# ReuseBlock___2025-12-05.net
KiCad netlist of a schematic drawn in EasyEDA Pro
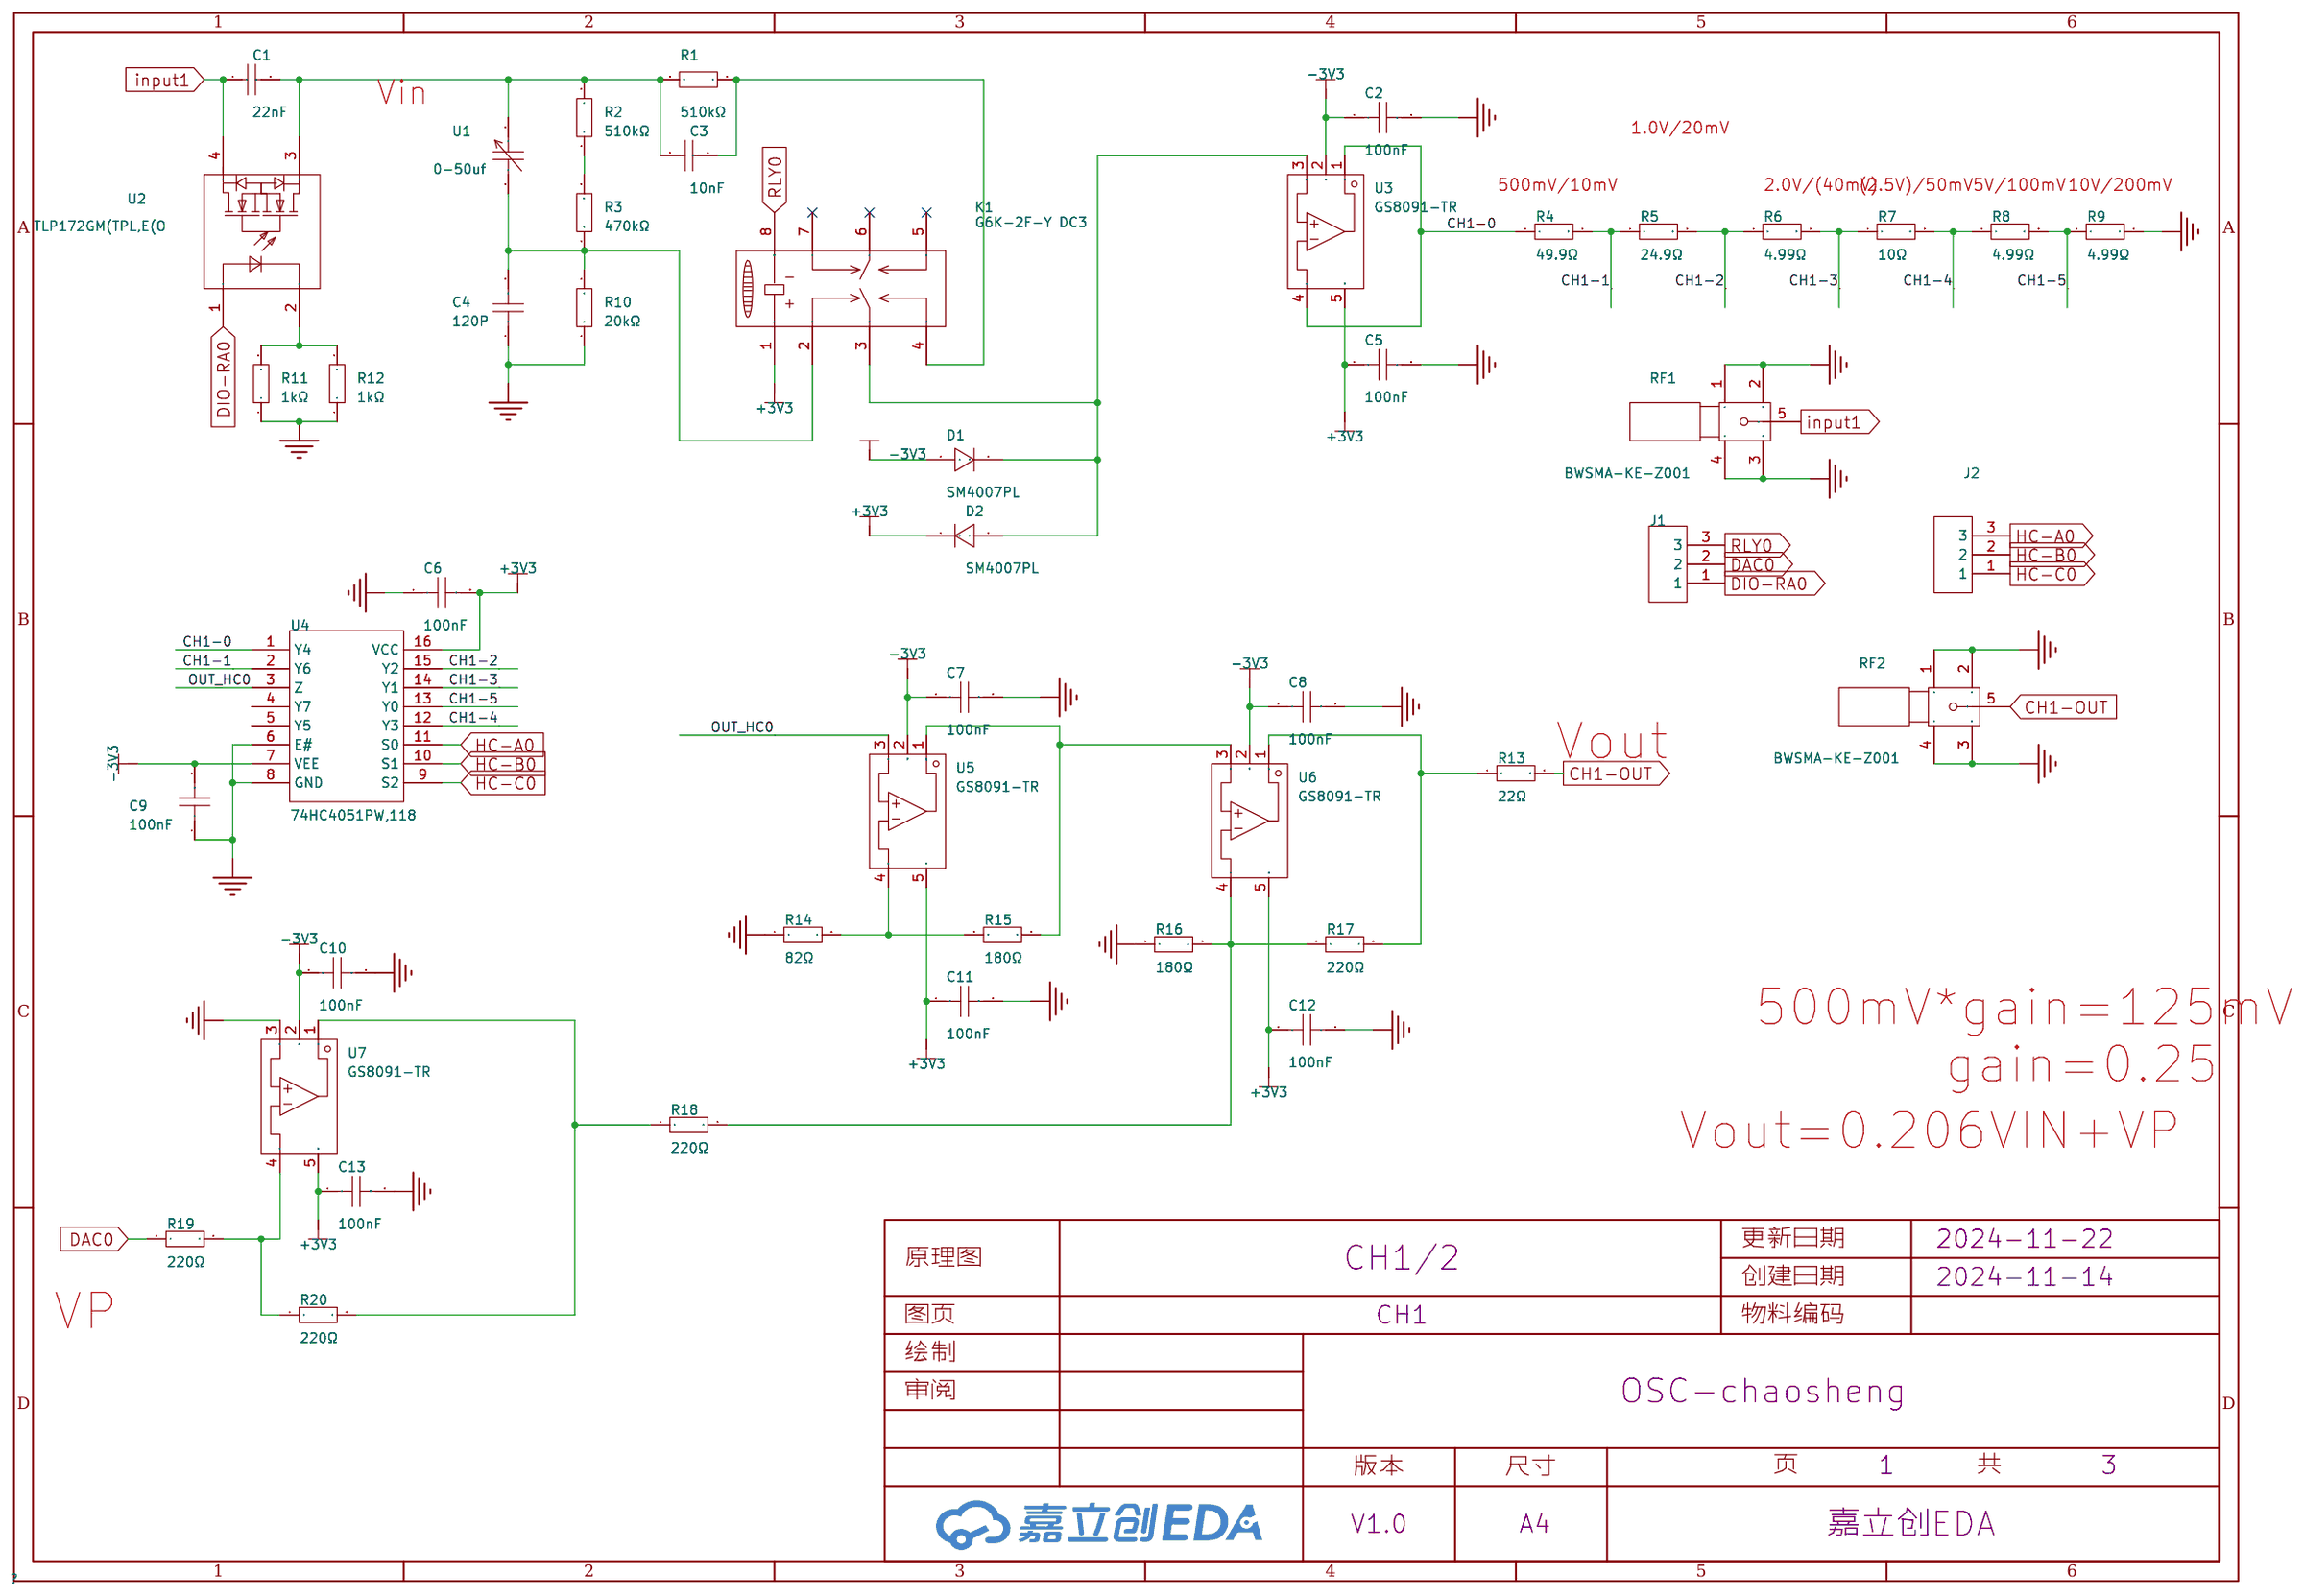
[diagram p0: CH1]
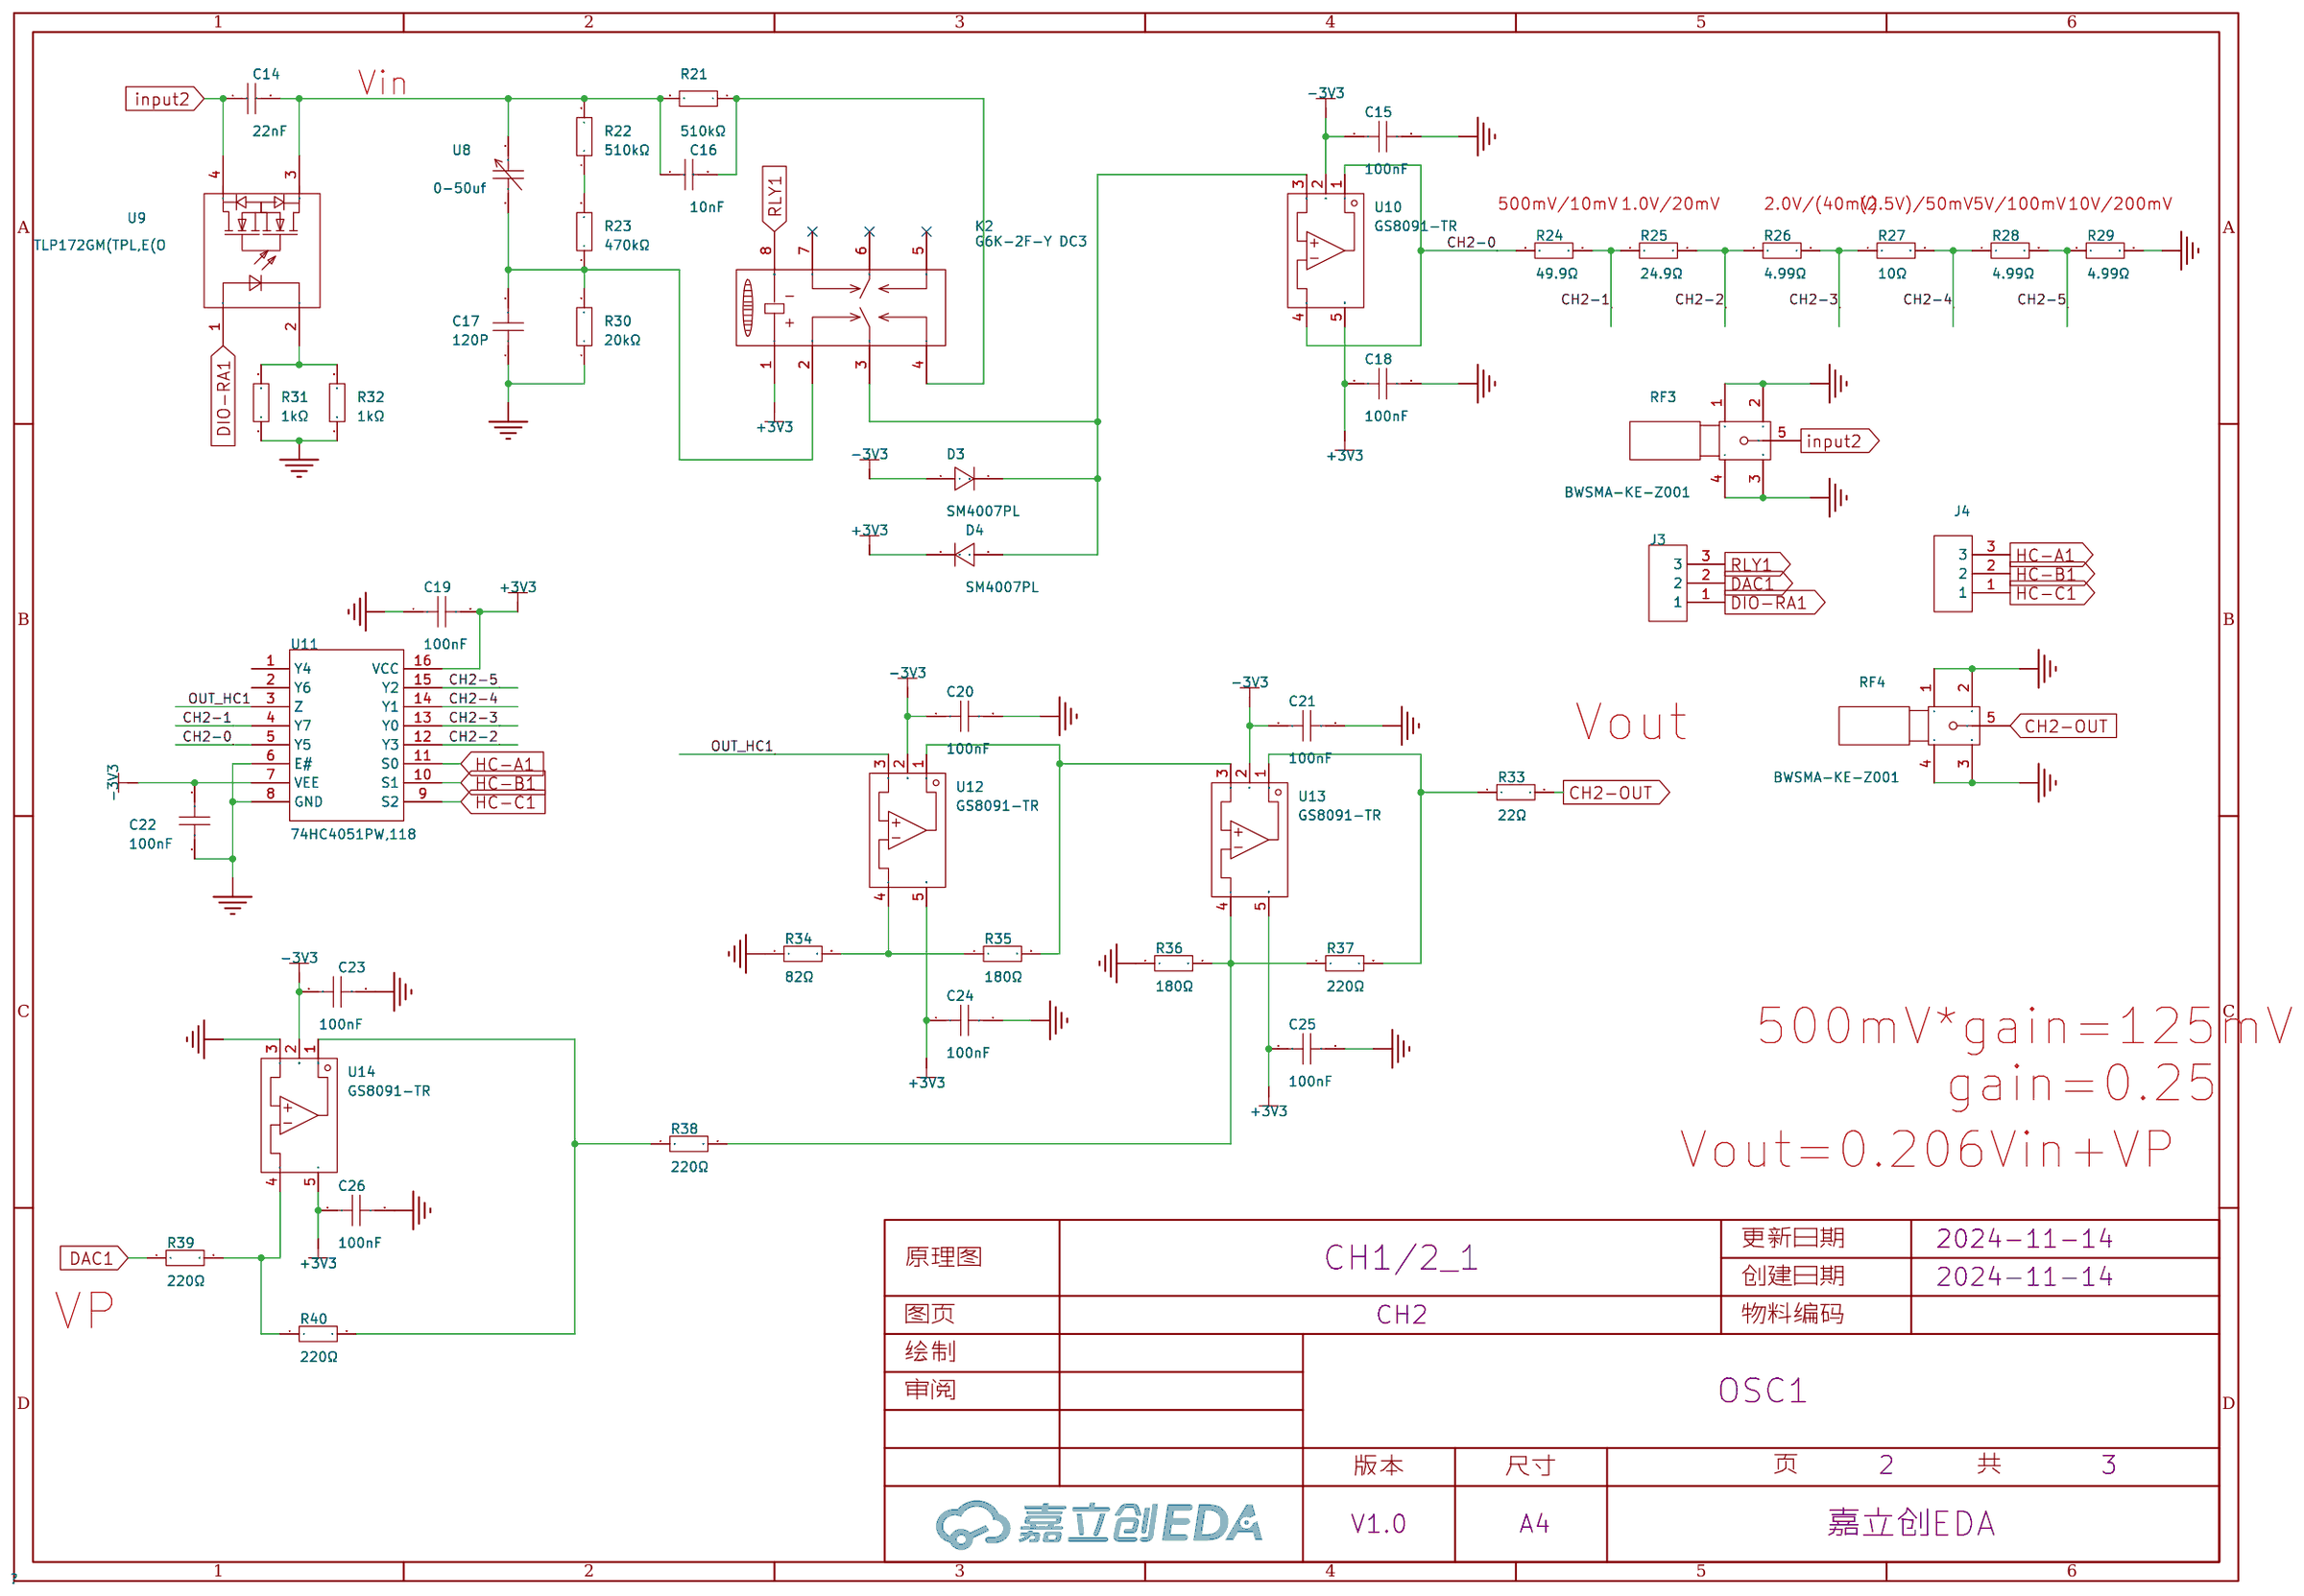
[diagram p1: CH2]
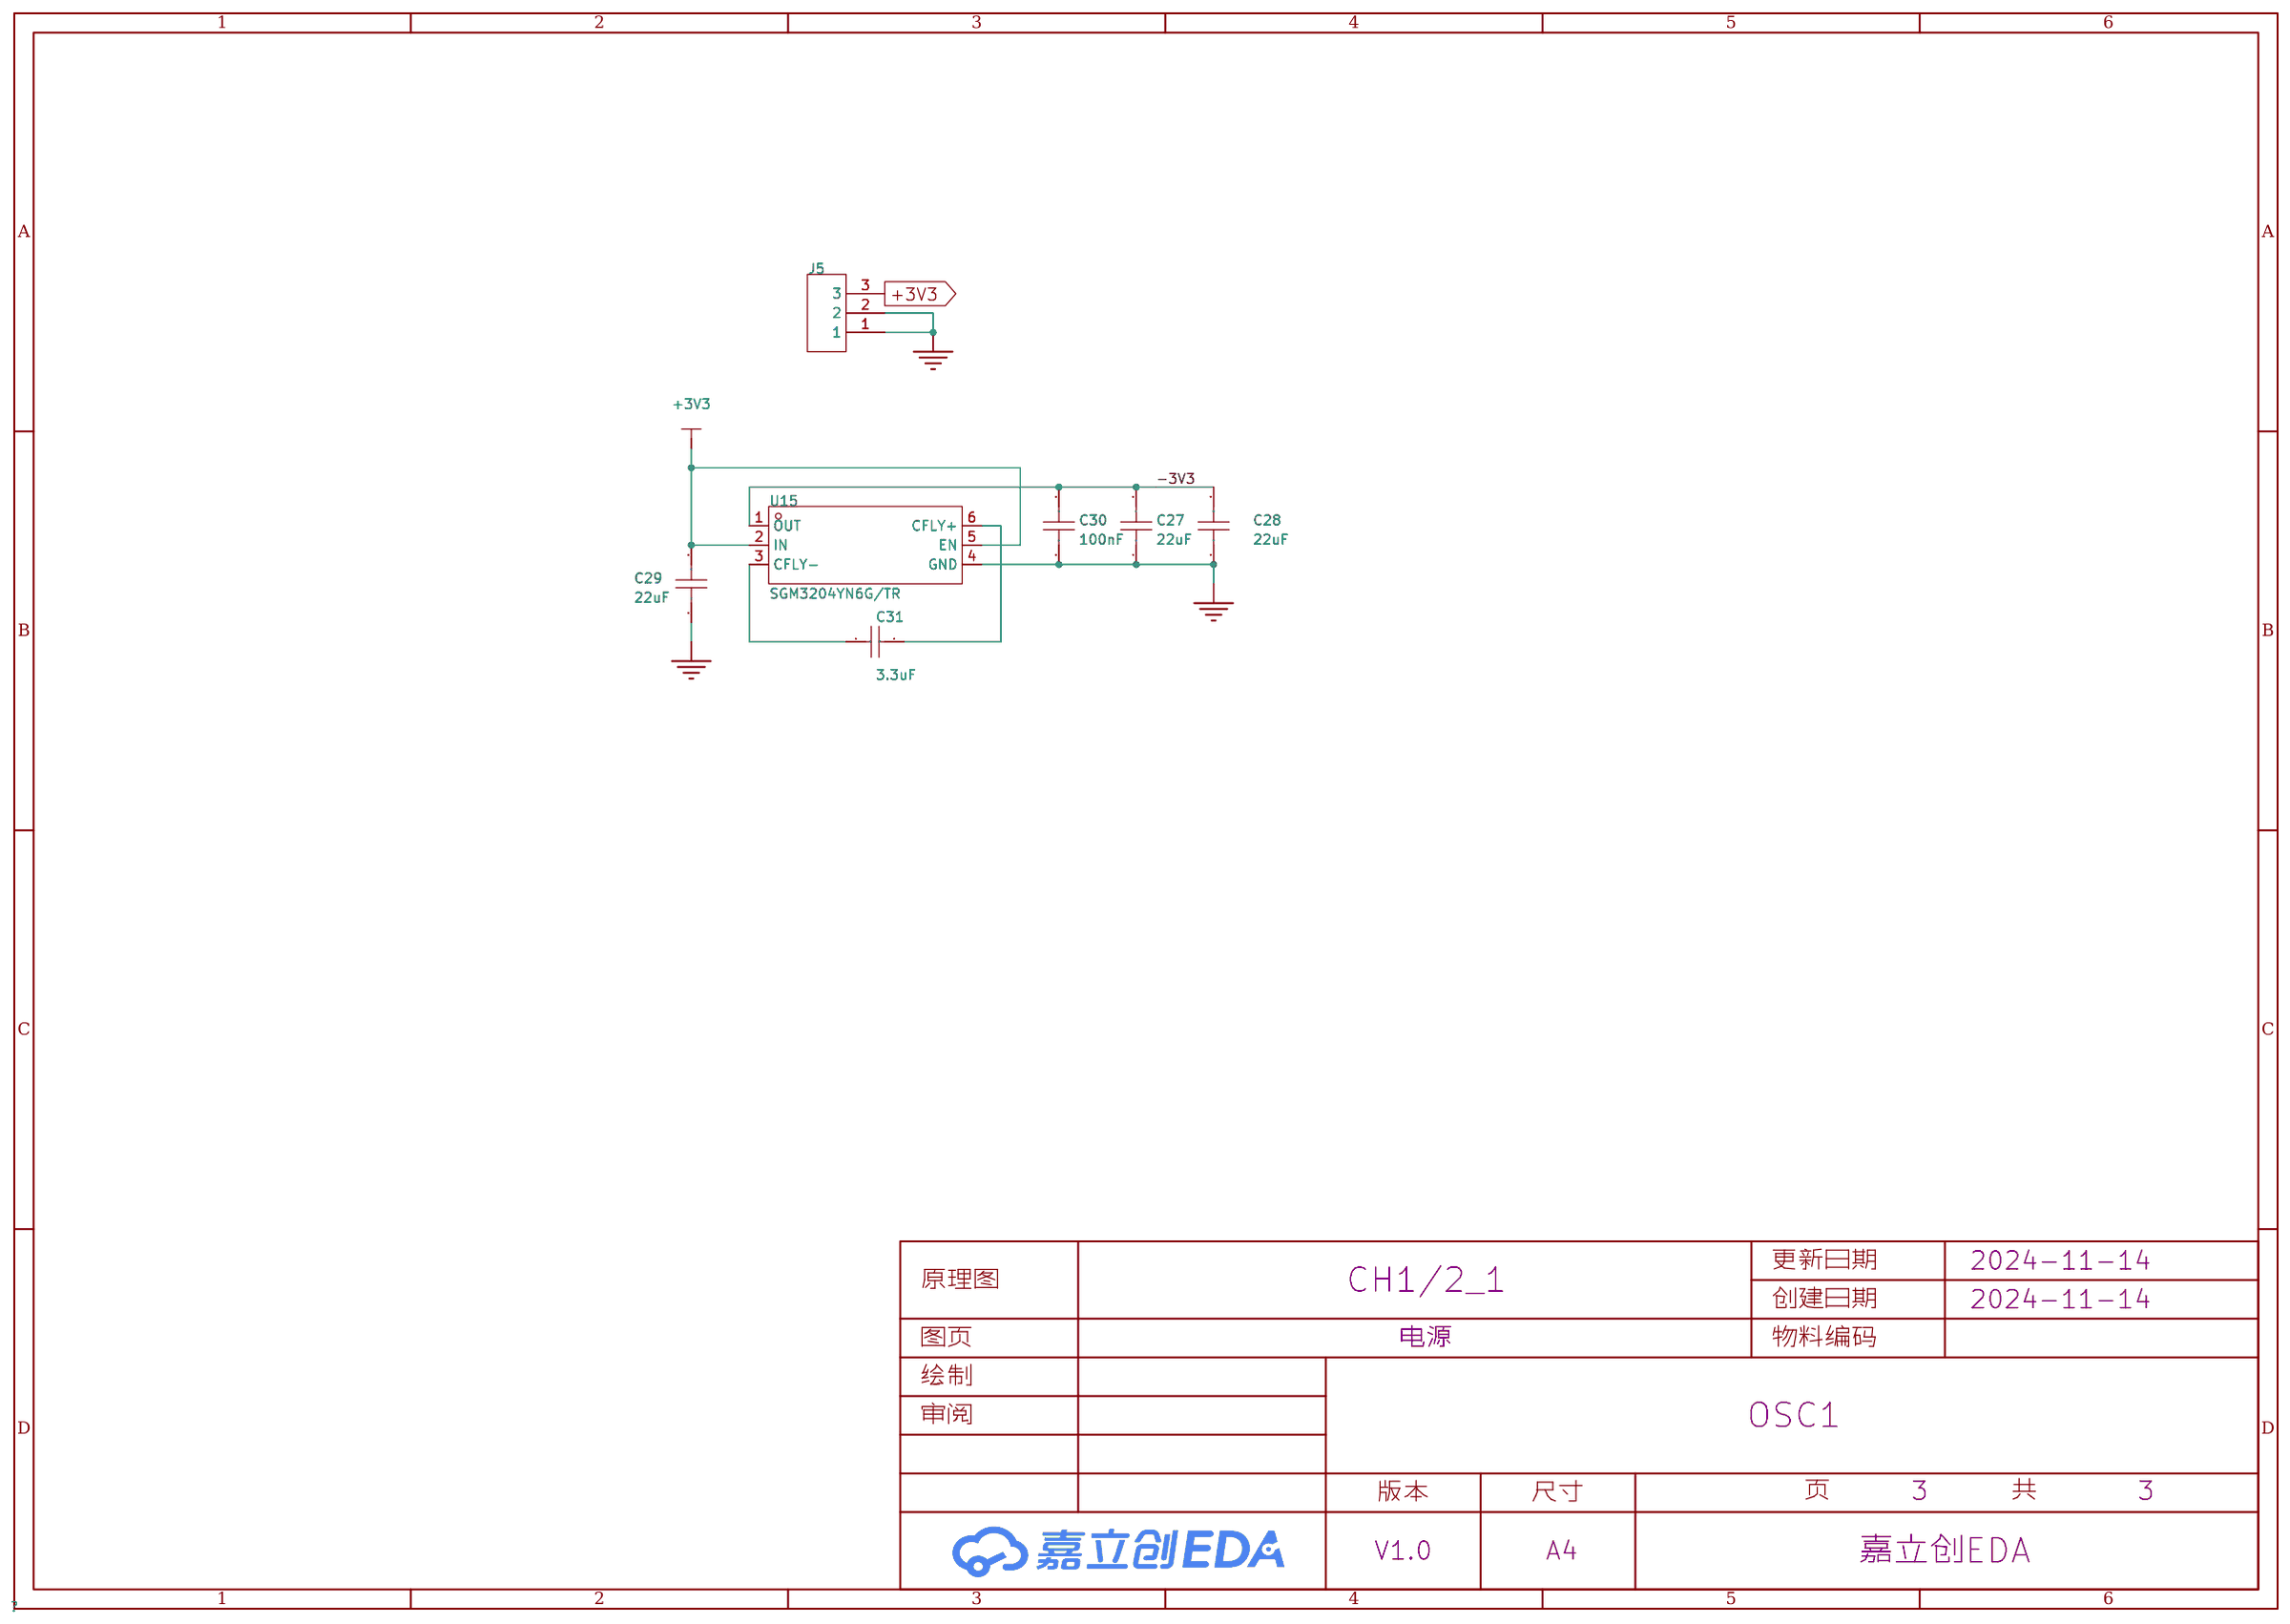
[diagram p2: 电源]

(export (version "E")
  (design (tool "Eeschema 10.0.6"))
  (components
    (comp (ref "C1")
      (value "22nF")
      (footprint "easyedapro:C0603")
      (description "容值:22nF;精度:±10%;额定电压:50V;材质(温度系数):X7R;")
      (fields
        (field (name "Manufacturer Part") "CL10B223KB8NNNC")
        (field (name "Manufacturer") "SAMSUNG(三星)")
      )
      (libsource (lib "easyedapro") (part "CL10B223KB8NNNC"))
    )
    (comp (ref "C2")
      (value "100nF")
      (footprint "easyedapro:C0402")
      (description "容值:100nF;精度:±10%;额定电压:50V;材质(温度系数):X7R;")
      (fields
        (field (name "Manufacturer Part") "CL05B104KB54PNC")
        (field (name "Manufacturer") "SAMSUNG(三星)")
      )
      (libsource (lib "easyedapro") (part "CL05B104KB54PNC"))
    )
    (comp (ref "C3")
      (value "10nF")
      (footprint "easyedapro:C0402")
      (description "容值:10nF;精度:±10%;额定电压:50V;材质(温度系数):X7R;")
      (fields
        (field (name "Manufacturer Part") "CL05B103KB5NNNC")
        (field (name "Manufacturer") "SAMSUNG(三星)")
      )
      (libsource (lib "easyedapro") (part "CL05B103KB5NNNC"))
    )
    (comp (ref "C4")
      (value "120P")
      (footprint "easyedapro:280*100mil")
      (libsource (lib "easyedapro") (part "插件电容"))
    )
    (comp (ref "C5")
      (value "100nF")
      (footprint "easyedapro:C0402")
      (description "容值:100nF;精度:±10%;额定电压:50V;材质(温度系数):X7R;")
      (fields
        (field (name "Manufacturer Part") "CL05B104KB54PNC")
        (field (name "Manufacturer") "SAMSUNG(三星)")
      )
      (libsource (lib "easyedapro") (part "CL05B104KB54PNC"))
    )
    (comp (ref "C6")
      (value "100nF")
      (footprint "easyedapro:C0402")
      (description "容值:100nF;精度:±10%;额定电压:50V;材质(温度系数):X7R;")
      (fields
        (field (name "Manufacturer Part") "CL05B104KB54PNC")
        (field (name "Manufacturer") "SAMSUNG(三星)")
      )
      (libsource (lib "easyedapro") (part "CL05B104KB54PNC"))
    )
    (comp (ref "C7")
      (value "100nF")
      (footprint "easyedapro:C0402")
      (description "容值:100nF;精度:±10%;额定电压:50V;材质(温度系数):X7R;")
      (fields
        (field (name "Manufacturer Part") "CL05B104KB54PNC")
        (field (name "Manufacturer") "SAMSUNG(三星)")
      )
      (libsource (lib "easyedapro") (part "CL05B104KB54PNC"))
    )
    (comp (ref "C8")
      (value "100nF")
      (footprint "easyedapro:C0402")
      (description "容值:100nF;精度:±10%;额定电压:50V;材质(温度系数):X7R;")
      (fields
        (field (name "Manufacturer Part") "CL05B104KB54PNC")
        (field (name "Manufacturer") "SAMSUNG(三星)")
      )
      (libsource (lib "easyedapro") (part "CL05B104KB54PNC"))
    )
    (comp (ref "C9")
      (value "100nF")
      (footprint "easyedapro:C0402")
      (description "容值:100nF;精度:±10%;额定电压:50V;材质(温度系数):X7R;")
      (fields
        (field (name "Manufacturer Part") "CL05B104KB54PNC")
        (field (name "Manufacturer") "SAMSUNG(三星)")
      )
      (libsource (lib "easyedapro") (part "CL05B104KB54PNC"))
    )
    (comp (ref "C10")
      (value "100nF")
      (footprint "easyedapro:C0402")
      (description "容值:100nF;精度:±10%;额定电压:50V;材质(温度系数):X7R;")
      (fields
        (field (name "Manufacturer Part") "CL05B104KB54PNC")
        (field (name "Manufacturer") "SAMSUNG(三星)")
      )
      (libsource (lib "easyedapro") (part "CL05B104KB54PNC"))
    )
    (comp (ref "C11")
      (value "100nF")
      (footprint "easyedapro:C0402")
      (description "容值:100nF;精度:±10%;额定电压:50V;材质(温度系数):X7R;")
      (fields
        (field (name "Manufacturer Part") "CL05B104KB54PNC")
        (field (name "Manufacturer") "SAMSUNG(三星)")
      )
      (libsource (lib "easyedapro") (part "CL05B104KB54PNC"))
    )
    (comp (ref "C12")
      (value "100nF")
      (footprint "easyedapro:C0402")
      (description "容值:100nF;精度:±10%;额定电压:50V;材质(温度系数):X7R;")
      (fields
        (field (name "Manufacturer Part") "CL05B104KB54PNC")
        (field (name "Manufacturer") "SAMSUNG(三星)")
      )
      (libsource (lib "easyedapro") (part "CL05B104KB54PNC"))
    )
    (comp (ref "C13")
      (value "100nF")
      (footprint "easyedapro:C0402")
      (description "容值:100nF;精度:±10%;额定电压:50V;材质(温度系数):X7R;")
      (fields
        (field (name "Manufacturer Part") "CL05B104KB54PNC")
        (field (name "Manufacturer") "SAMSUNG(三星)")
      )
      (libsource (lib "easyedapro") (part "CL05B104KB54PNC"))
    )
    (comp (ref "D1")
      (value "SM4007PL")
      (footprint "easyedapro:SOD-123F_L2.8-W1.8-LS3.7-RD")
      (description "二极管配置:独立式;正向压降(Vf):1.1V@1A;直流反向耐压(Vr):1kV;整流电流:1A;")
      (fields (field (name "Manufacturer") "MDD(辰达半导体)"))
      (libsource (lib "easyedapro") (part "SM4007PL"))
    )
    (comp (ref "D2")
      (value "SM4007PL")
      (footprint "easyedapro:SOD-123F_L2.8-W1.8-LS3.7-RD")
      (description "二极管配置:独立式;正向压降(Vf):1.1V@1A;直流反向耐压(Vr):1kV;整流电流:1A;")
      (fields (field (name "Manufacturer") "MDD(辰达半导体)"))
      (libsource (lib "easyedapro") (part "SM4007PL"))
    )
    (comp (ref "J1")
      (value "~")
      (footprint "easyedapro:CH2.54-3插座")
      (libsource (lib "easyedapro") (part "HDR-3P"))
    )
    (comp (ref "J2")
      (value "~")
      (footprint "easyedapro:CH2.54-3插座")
      (libsource (lib "easyedapro") (part "HDR-3P"))
    )
    (comp (ref "K1")
      (value "G6K-2F-Y DC3")
      (footprint "easyedapro:RELAY-SMD_G6K-2F-Y")
      (description "线圈电压:-;触点形式:-;触点容量(电阻负载):-;最大切换电压:-;最大切换电流:-;")
      (fields (field (name "Manufacturer") "OMRON(欧姆龙)"))
      (libsource (lib "easyedapro") (part "G6K-2F-Y3VDC"))
    )
    (comp (ref "R1")
      (value "510kΩ")
      (footprint "easyedapro:R0402")
      (description "电阻类型:厚膜电阻;阻值:510kΩ;精度:±1%;功率:62.5mW;最大工作电压:50V;温度系数:±100ppm/°C;")
      (fields
        (field (name "Manufacturer Part") "0402WGF5103TCE")
        (field (name "Manufacturer") "UNI-ROYAL(厚声)")
      )
      (libsource (lib "easyedapro") (part "0402WGF5103TCE"))
    )
    (comp (ref "R2")
      (value "510kΩ")
      (footprint "easyedapro:R0402")
      (description "电阻类型:厚膜电阻;阻值:510kΩ;精度:±1%;功率:62.5mW;最大工作电压:50V;温度系数:±100ppm/°C;")
      (fields
        (field (name "Manufacturer Part") "0402WGF5103TCE")
        (field (name "Manufacturer") "UNI-ROYAL(厚声)")
      )
      (libsource (lib "easyedapro") (part "0402WGF5103TCE"))
    )
    (comp (ref "R3")
      (value "470kΩ")
      (footprint "easyedapro:R0402")
      (description "电阻类型:厚膜电阻;阻值:470kΩ;精度:±1%;功率:62.5mW;最大工作电压:50V;温度系数:±100ppm/°C;")
      (fields
        (field (name "Manufacturer Part") "0402WGF4703TCE")
        (field (name "Manufacturer") "UNI-ROYAL(厚声)")
      )
      (libsource (lib "easyedapro") (part "0402WGF4703TCE"))
    )
    (comp (ref "R4")
      (value "49.9Ω")
      (footprint "easyedapro:R0402")
      (description "电阻类型:厚膜电阻;阻值:49.9Ω;精度:±1%;功率:62.5mW;最大工作电压:50V;温度系数:±100ppm/°C;")
      (fields
        (field (name "Manufacturer Part") "0402WGF499JTCE")
        (field (name "Manufacturer") "UNI-ROYAL(厚声)")
      )
      (libsource (lib "easyedapro") (part "0402WGF499JTCE"))
    )
    (comp (ref "R5")
      (value "24.9Ω")
      (footprint "easyedapro:R0402")
      (description "电阻类型:厚膜电阻;阻值:24.9Ω;精度:±1%;功率:62.5mW;最大工作电压:50V;温度系数:±200ppm/°C;")
      (fields
        (field (name "Manufacturer Part") "0402WGF249JTCE")
        (field (name "Manufacturer") "UNI-ROYAL(厚声)")
      )
      (libsource (lib "easyedapro") (part "0402WGF249JTCE"))
    )
    (comp (ref "R6")
      (value "4.99Ω")
      (footprint "easyedapro:R0402")
      (description "电阻类型:厚膜电阻;阻值:4.99Ω;精度:±1%;功率:62.5mW;最大工作电压:50V;温度系数:±400ppm/°C;")
      (fields
        (field (name "Manufacturer Part") "0402WGF499KTCE")
        (field (name "Manufacturer") "UNI-ROYAL(厚声)")
      )
      (libsource (lib "easyedapro") (part "0402WGF499KTCE"))
    )
    (comp (ref "R7")
      (value "10Ω")
      (footprint "easyedapro:R0402")
      (description "电阻类型:厚膜电阻;阻值:10Ω;精度:±1%;功率:62.5mW;最大工作电压:50V;温度系数:±200ppm/°C;")
      (fields
        (field (name "Manufacturer Part") "0402WGF100JTCE")
        (field (name "Manufacturer") "UNI-ROYAL(厚声)")
      )
      (libsource (lib "easyedapro") (part "0402WGF100JTCE"))
    )
    (comp (ref "R8")
      (value "4.99Ω")
      (footprint "easyedapro:R0402")
      (description "电阻类型:厚膜电阻;阻值:4.99Ω;精度:±1%;功率:62.5mW;最大工作电压:50V;温度系数:±400ppm/°C;")
      (fields
        (field (name "Manufacturer Part") "0402WGF499KTCE")
        (field (name "Manufacturer") "UNI-ROYAL(厚声)")
      )
      (libsource (lib "easyedapro") (part "0402WGF499KTCE"))
    )
    (comp (ref "R9")
      (value "4.99Ω")
      (footprint "easyedapro:R0402")
      (description "电阻类型:厚膜电阻;阻值:4.99Ω;精度:±1%;功率:62.5mW;最大工作电压:50V;温度系数:±400ppm/°C;")
      (fields
        (field (name "Manufacturer Part") "0402WGF499KTCE")
        (field (name "Manufacturer") "UNI-ROYAL(厚声)")
      )
      (libsource (lib "easyedapro") (part "0402WGF499KTCE"))
    )
    (comp (ref "R10")
      (value "20kΩ")
      (footprint "easyedapro:R0402")
      (description "电阻类型:厚膜电阻;阻值:20kΩ;精度:±1%;功率:62.5mW;最大工作电压:50V;温度系数:±100ppm/°C;")
      (fields
        (field (name "Manufacturer Part") "0402WGF2002TCE")
        (field (name "Manufacturer") "UNI-ROYAL(厚声)")
      )
      (libsource (lib "easyedapro") (part "0402WGF2002TCE"))
    )
    (comp (ref "R11")
      (value "1kΩ")
      (footprint "easyedapro:R0402")
      (description "电阻类型:厚膜电阻;阻值:1kΩ;精度:±1%;功率:62.5mW;最大工作电压:50V;温度系数:±100ppm/°C;")
      (fields
        (field (name "Manufacturer Part") "0402WGF1001TCE")
        (field (name "Manufacturer") "UNI-ROYAL(厚声)")
      )
      (libsource (lib "easyedapro") (part "0402WGF1001TCE"))
    )
    (comp (ref "R12")
      (value "1kΩ")
      (footprint "easyedapro:R0402")
      (description "电阻类型:厚膜电阻;阻值:1kΩ;精度:±1%;功率:62.5mW;最大工作电压:50V;温度系数:±100ppm/°C;")
      (fields
        (field (name "Manufacturer Part") "0402WGF1001TCE")
        (field (name "Manufacturer") "UNI-ROYAL(厚声)")
      )
      (libsource (lib "easyedapro") (part "0402WGF1001TCE"))
    )
    (comp (ref "R13")
      (value "22Ω")
      (footprint "easyedapro:R0402")
      (description "电阻类型:厚膜电阻;阻值:22Ω;精度:±1%;功率:62.5mW;最大工作电压:50V;温度系数:±100ppm/°C;")
      (fields
        (field (name "Manufacturer Part") "0402WGF220JTCE")
        (field (name "Manufacturer") "UNI-ROYAL(厚声)")
      )
      (libsource (lib "easyedapro") (part "0402WGF220JTCE"))
    )
    (comp (ref "R14")
      (value "82Ω")
      (footprint "easyedapro:R0402")
      (description "电阻类型:厚膜电阻;阻值:82Ω;精度:±1%;功率:62.5mW;最大工作电压:50V;温度系数:±200ppm/°C;")
      (fields
        (field (name "Manufacturer Part") "0402WGF820JTCE")
        (field (name "Manufacturer") "UNI-ROYAL(厚声)")
      )
      (libsource (lib "easyedapro") (part "0402WGF820JTCE"))
    )
    (comp (ref "R15")
      (value "180Ω")
      (footprint "easyedapro:R0402")
      (description "电阻类型:厚膜电阻;阻值:180Ω;精度:±1%;功率:62.5mW;最大工作电压:50V;温度系数:±100ppm/°C;")
      (fields
        (field (name "Manufacturer Part") "0402WGF1800TCE")
        (field (name "Manufacturer") "UNI-ROYAL(厚声)")
      )
      (libsource (lib "easyedapro") (part "0402WGF1800TCE"))
    )
    (comp (ref "R16")
      (value "180Ω")
      (footprint "easyedapro:R0402")
      (description "电阻类型:厚膜电阻;阻值:180Ω;精度:±1%;功率:62.5mW;最大工作电压:50V;温度系数:±100ppm/°C;")
      (fields
        (field (name "Manufacturer Part") "0402WGF1800TCE")
        (field (name "Manufacturer") "UNI-ROYAL(厚声)")
      )
      (libsource (lib "easyedapro") (part "0402WGF1800TCE"))
    )
    (comp (ref "R17")
      (value "220Ω")
      (footprint "easyedapro:R0402")
      (description "电阻类型:厚膜电阻;阻值:220Ω;精度:±1%;功率:62.5mW;最大工作电压:50V;温度系数:±100ppm/°C;")
      (fields
        (field (name "Manufacturer Part") "0402WGF2200TCE")
        (field (name "Manufacturer") "UNI-ROYAL(厚声)")
      )
      (libsource (lib "easyedapro") (part "0402WGF2200TCE"))
    )
    (comp (ref "R18")
      (value "220Ω")
      (footprint "easyedapro:R0402")
      (description "电阻类型:厚膜电阻;阻值:220Ω;精度:±1%;功率:62.5mW;最大工作电压:50V;温度系数:±100ppm/°C;")
      (fields
        (field (name "Manufacturer Part") "0402WGF2200TCE")
        (field (name "Manufacturer") "UNI-ROYAL(厚声)")
      )
      (libsource (lib "easyedapro") (part "0402WGF2200TCE"))
    )
    (comp (ref "R19")
      (value "220Ω")
      (footprint "easyedapro:R0402")
      (description "电阻类型:厚膜电阻;阻值:220Ω;精度:±1%;功率:62.5mW;最大工作电压:50V;温度系数:±100ppm/°C;")
      (fields
        (field (name "Manufacturer Part") "0402WGF2200TCE")
        (field (name "Manufacturer") "UNI-ROYAL(厚声)")
      )
      (libsource (lib "easyedapro") (part "0402WGF2200TCE"))
    )
    (comp (ref "R20")
      (value "220Ω")
      (footprint "easyedapro:R0402")
      (description "电阻类型:厚膜电阻;阻值:220Ω;精度:±1%;功率:62.5mW;最大工作电压:50V;温度系数:±100ppm/°C;")
      (fields
        (field (name "Manufacturer Part") "0402WGF2200TCE")
        (field (name "Manufacturer") "UNI-ROYAL(厚声)")
      )
      (libsource (lib "easyedapro") (part "0402WGF2200TCE"))
    )
    (comp (ref "RF1")
      (value "BWSMA-KE-Z001")
      (footprint "easyedapro:SMA-TH_BWSMA-KE-Z001")
      (fields (field (name "Manufacturer") "BAT WIRELESS(蝙蝠无线)"))
      (libsource (lib "easyedapro") (part "BWSMA-KE-Z001"))
    )
    (comp (ref "RF2")
      (value "BWSMA-KE-Z001")
      (footprint "easyedapro:SMA-TH_BWSMA-KE-Z001")
      (fields (field (name "Manufacturer") "BAT WIRELESS(蝙蝠无线)"))
      (libsource (lib "easyedapro") (part "BWSMA-KE-Z001"))
    )
    (comp (ref "U1")
      (value "0-50uf")
      (footprint "easyedapro:可调电容")
      (libsource (lib "easyedapro") (part "0-50uf可调电容"))
    )
    (comp (ref "U2")
      (value "TLP172GM(TPL,E(O")
      (footprint "easyedapro:SMD-4_L4.6-W3.7-P2.54-LS7.0-BR")
      (description "继电器触点形式:1 Form A(SPST-NO);适用负载类型:AC,DC;正向压降:1.27V;负载电压:350V;连续负载电流:110mA;导通电阻:22Ω;")
      (fields (field (name "Manufacturer") "TOSHIBA(东芝)"))
      (libsource (lib "easyedapro") (part "TLP172GM(TPL,E(O"))
    )
    (comp (ref "U3")
      (value "GS8091-TR")
      (footprint "easyedapro:SOT-23-5_L3.0-W1.7-P0.95-LS2.8-BR")
      (description "放大器数:单路;增益带宽积(GBP):180MHz;输入偏置电流(Ib):1pA;输入失调电压(Vos):2mV;压摆率(SR):206V/us;带宽(-3db):350MHz;")
      (fields (field (name "Manufacturer") "Gainsil(聚洵)"))
      (libsource (lib "easyedapro") (part "GS8091-TR"))
    )
    (comp (ref "U4")
      (value "74HC4051PW,118")
      (footprint "easyedapro:TSSOP-16_L5.0-W4.4-P0.65-LS6.4-BL")
      (description "通道数:1;导通电阻(Ron@VCC):120Ω;")
      (fields (field (name "Manufacturer") "Nexperia(安世)"))
      (libsource (lib "easyedapro") (part "74HC4051PW,118"))
    )
    (comp (ref "U5")
      (value "GS8091-TR")
      (footprint "easyedapro:SOT-23-5_L3.0-W1.7-P0.95-LS2.8-BR")
      (description "放大器数:单路;增益带宽积(GBP):180MHz;输入偏置电流(Ib):1pA;输入失调电压(Vos):2mV;压摆率(SR):206V/us;带宽(-3db):350MHz;")
      (fields (field (name "Manufacturer") "Gainsil(聚洵)"))
      (libsource (lib "easyedapro") (part "GS8091-TR"))
    )
    (comp (ref "U6")
      (value "GS8091-TR")
      (footprint "easyedapro:SOT-23-5_L3.0-W1.7-P0.95-LS2.8-BR")
      (description "放大器数:单路;增益带宽积(GBP):180MHz;输入偏置电流(Ib):1pA;输入失调电压(Vos):2mV;压摆率(SR):206V/us;带宽(-3db):350MHz;")
      (fields (field (name "Manufacturer") "Gainsil(聚洵)"))
      (libsource (lib "easyedapro") (part "GS8091-TR"))
    )
    (comp (ref "U7")
      (value "GS8091-TR")
      (footprint "easyedapro:SOT-23-5_L3.0-W1.7-P0.95-LS2.8-BR")
      (description "放大器数:单路;增益带宽积(GBP):180MHz;输入偏置电流(Ib):1pA;输入失调电压(Vos):2mV;压摆率(SR):206V/us;带宽(-3db):350MHz;")
      (fields (field (name "Manufacturer") "Gainsil(聚洵)"))
      (libsource (lib "easyedapro") (part "GS8091-TR"))
    )
    (comp (ref "C14")
      (value "22nF")
      (footprint "easyedapro:C0603")
      (description "容值:22nF;精度:±10%;额定电压:50V;材质(温度系数):X7R;")
      (fields
        (field (name "Manufacturer Part") "CL10B223KB8NNNC")
        (field (name "Manufacturer") "SAMSUNG(三星)")
      )
      (libsource (lib "easyedapro") (part "CL10B223KB8NNNC"))
    )
    (comp (ref "C15")
      (value "100nF")
      (footprint "easyedapro:C0402")
      (description "容值:100nF;精度:±10%;额定电压:50V;材质(温度系数):X7R;")
      (fields
        (field (name "Manufacturer Part") "CL05B104KB54PNC")
        (field (name "Manufacturer") "SAMSUNG(三星)")
      )
      (libsource (lib "easyedapro") (part "CL05B104KB54PNC"))
    )
    (comp (ref "C16")
      (value "10nF")
      (footprint "easyedapro:C0402")
      (description "容值:10nF;精度:±10%;额定电压:50V;材质(温度系数):X7R;")
      (fields
        (field (name "Manufacturer Part") "CL05B103KB5NNNC")
        (field (name "Manufacturer") "SAMSUNG(三星)")
      )
      (libsource (lib "easyedapro") (part "CL05B103KB5NNNC"))
    )
    (comp (ref "C17")
      (value "120P")
      (footprint "easyedapro:280*100mil")
      (libsource (lib "easyedapro") (part "插件电容"))
    )
    (comp (ref "C18")
      (value "100nF")
      (footprint "easyedapro:C0402")
      (description "容值:100nF;精度:±10%;额定电压:50V;材质(温度系数):X7R;")
      (fields
        (field (name "Manufacturer Part") "CL05B104KB54PNC")
        (field (name "Manufacturer") "SAMSUNG(三星)")
      )
      (libsource (lib "easyedapro") (part "CL05B104KB54PNC"))
    )
    (comp (ref "C19")
      (value "100nF")
      (footprint "easyedapro:C0402")
      (description "容值:100nF;精度:±10%;额定电压:50V;材质(温度系数):X7R;")
      (fields
        (field (name "Manufacturer Part") "CL05B104KB54PNC")
        (field (name "Manufacturer") "SAMSUNG(三星)")
      )
      (libsource (lib "easyedapro") (part "CL05B104KB54PNC"))
    )
    (comp (ref "C20")
      (value "100nF")
      (footprint "easyedapro:C0402")
      (description "容值:100nF;精度:±10%;额定电压:50V;材质(温度系数):X7R;")
      (fields
        (field (name "Manufacturer Part") "CL05B104KB54PNC")
        (field (name "Manufacturer") "SAMSUNG(三星)")
      )
      (libsource (lib "easyedapro") (part "CL05B104KB54PNC"))
    )
    (comp (ref "C21")
      (value "100nF")
      (footprint "easyedapro:C0402")
      (description "容值:100nF;精度:±10%;额定电压:50V;材质(温度系数):X7R;")
      (fields
        (field (name "Manufacturer Part") "CL05B104KB54PNC")
        (field (name "Manufacturer") "SAMSUNG(三星)")
      )
      (libsource (lib "easyedapro") (part "CL05B104KB54PNC"))
    )
    (comp (ref "C22")
      (value "100nF")
      (footprint "easyedapro:C0402")
      (description "容值:100nF;精度:±10%;额定电压:50V;材质(温度系数):X7R;")
      (fields
        (field (name "Manufacturer Part") "CL05B104KB54PNC")
        (field (name "Manufacturer") "SAMSUNG(三星)")
      )
      (libsource (lib "easyedapro") (part "CL05B104KB54PNC"))
    )
    (comp (ref "C23")
      (value "100nF")
      (footprint "easyedapro:C0402")
      (description "容值:100nF;精度:±10%;额定电压:50V;材质(温度系数):X7R;")
      (fields
        (field (name "Manufacturer Part") "CL05B104KB54PNC")
        (field (name "Manufacturer") "SAMSUNG(三星)")
      )
      (libsource (lib "easyedapro") (part "CL05B104KB54PNC"))
    )
    (comp (ref "C24")
      (value "100nF")
      (footprint "easyedapro:C0402")
      (description "容值:100nF;精度:±10%;额定电压:50V;材质(温度系数):X7R;")
      (fields
        (field (name "Manufacturer Part") "CL05B104KB54PNC")
        (field (name "Manufacturer") "SAMSUNG(三星)")
      )
      (libsource (lib "easyedapro") (part "CL05B104KB54PNC"))
    )
    (comp (ref "C25")
      (value "100nF")
      (footprint "easyedapro:C0402")
      (description "容值:100nF;精度:±10%;额定电压:50V;材质(温度系数):X7R;")
      (fields
        (field (name "Manufacturer Part") "CL05B104KB54PNC")
        (field (name "Manufacturer") "SAMSUNG(三星)")
      )
      (libsource (lib "easyedapro") (part "CL05B104KB54PNC"))
    )
    (comp (ref "C26")
      (value "100nF")
      (footprint "easyedapro:C0402")
      (description "容值:100nF;精度:±10%;额定电压:50V;材质(温度系数):X7R;")
      (fields
        (field (name "Manufacturer Part") "CL05B104KB54PNC")
        (field (name "Manufacturer") "SAMSUNG(三星)")
      )
      (libsource (lib "easyedapro") (part "CL05B104KB54PNC"))
    )
    (comp (ref "D3")
      (value "SM4007PL")
      (footprint "easyedapro:SOD-123F_L2.8-W1.8-LS3.7-RD")
      (description "二极管配置:独立式;正向压降(Vf):1.1V@1A;直流反向耐压(Vr):1kV;整流电流:1A;")
      (fields (field (name "Manufacturer") "MDD(辰达半导体)"))
      (libsource (lib "easyedapro") (part "SM4007PL"))
    )
    (comp (ref "D4")
      (value "SM4007PL")
      (footprint "easyedapro:SOD-123F_L2.8-W1.8-LS3.7-RD")
      (description "二极管配置:独立式;正向压降(Vf):1.1V@1A;直流反向耐压(Vr):1kV;整流电流:1A;")
      (fields (field (name "Manufacturer") "MDD(辰达半导体)"))
      (libsource (lib "easyedapro") (part "SM4007PL"))
    )
    (comp (ref "J3")
      (value "~")
      (footprint "easyedapro:CH2.54-3插座")
      (libsource (lib "easyedapro") (part "HDR-3P"))
    )
    (comp (ref "J4")
      (value "~")
      (footprint "easyedapro:CH2.54-3插座")
      (libsource (lib "easyedapro") (part "HDR-3P"))
    )
    (comp (ref "K2")
      (value "G6K-2F-Y DC3")
      (footprint "easyedapro:RELAY-SMD_G6K-2F-Y")
      (description "线圈电压:-;触点形式:-;触点容量(电阻负载):-;最大切换电压:-;最大切换电流:-;")
      (fields (field (name "Manufacturer") "OMRON(欧姆龙)"))
      (libsource (lib "easyedapro") (part "G6K-2F-Y3VDC"))
    )
    (comp (ref "R21")
      (value "510kΩ")
      (footprint "easyedapro:R0402")
      (description "电阻类型:厚膜电阻;阻值:510kΩ;精度:±1%;功率:62.5mW;最大工作电压:50V;温度系数:±100ppm/°C;")
      (fields
        (field (name "Manufacturer Part") "0402WGF5103TCE")
        (field (name "Manufacturer") "UNI-ROYAL(厚声)")
      )
      (libsource (lib "easyedapro") (part "0402WGF5103TCE"))
    )
    (comp (ref "R22")
      (value "510kΩ")
      (footprint "easyedapro:R0402")
      (description "电阻类型:厚膜电阻;阻值:510kΩ;精度:±1%;功率:62.5mW;最大工作电压:50V;温度系数:±100ppm/°C;")
      (fields
        (field (name "Manufacturer Part") "0402WGF5103TCE")
        (field (name "Manufacturer") "UNI-ROYAL(厚声)")
      )
      (libsource (lib "easyedapro") (part "0402WGF5103TCE"))
    )
    (comp (ref "R23")
      (value "470kΩ")
      (footprint "easyedapro:R0402")
      (description "电阻类型:厚膜电阻;阻值:470kΩ;精度:±1%;功率:62.5mW;最大工作电压:50V;温度系数:±100ppm/°C;")
      (fields
        (field (name "Manufacturer Part") "0402WGF4703TCE")
        (field (name "Manufacturer") "UNI-ROYAL(厚声)")
      )
      (libsource (lib "easyedapro") (part "0402WGF4703TCE"))
    )
    (comp (ref "R24")
      (value "49.9Ω")
      (footprint "easyedapro:R0402")
      (description "电阻类型:厚膜电阻;阻值:49.9Ω;精度:±1%;功率:62.5mW;最大工作电压:50V;温度系数:±100ppm/°C;")
      (fields
        (field (name "Manufacturer Part") "0402WGF499JTCE")
        (field (name "Manufacturer") "UNI-ROYAL(厚声)")
      )
      (libsource (lib "easyedapro") (part "0402WGF499JTCE"))
    )
    (comp (ref "R25")
      (value "24.9Ω")
      (footprint "easyedapro:R0402")
      (description "电阻类型:厚膜电阻;阻值:24.9Ω;精度:±1%;功率:62.5mW;最大工作电压:50V;温度系数:±200ppm/°C;")
      (fields
        (field (name "Manufacturer Part") "0402WGF249JTCE")
        (field (name "Manufacturer") "UNI-ROYAL(厚声)")
      )
      (libsource (lib "easyedapro") (part "0402WGF249JTCE"))
    )
    (comp (ref "R26")
      (value "4.99Ω")
      (footprint "easyedapro:R0402")
      (description "电阻类型:厚膜电阻;阻值:4.99Ω;精度:±1%;功率:62.5mW;最大工作电压:50V;温度系数:±400ppm/°C;")
      (fields
        (field (name "Manufacturer Part") "0402WGF499KTCE")
        (field (name "Manufacturer") "UNI-ROYAL(厚声)")
      )
      (libsource (lib "easyedapro") (part "0402WGF499KTCE"))
    )
    (comp (ref "R27")
      (value "10Ω")
      (footprint "easyedapro:R0402")
      (description "电阻类型:厚膜电阻;阻值:10Ω;精度:±1%;功率:62.5mW;最大工作电压:50V;温度系数:±200ppm/°C;")
      (fields
        (field (name "Manufacturer Part") "0402WGF100JTCE")
        (field (name "Manufacturer") "UNI-ROYAL(厚声)")
      )
      (libsource (lib "easyedapro") (part "0402WGF100JTCE"))
    )
    (comp (ref "R28")
      (value "4.99Ω")
      (footprint "easyedapro:R0402")
      (description "电阻类型:厚膜电阻;阻值:4.99Ω;精度:±1%;功率:62.5mW;最大工作电压:50V;温度系数:±400ppm/°C;")
      (fields
        (field (name "Manufacturer Part") "0402WGF499KTCE")
        (field (name "Manufacturer") "UNI-ROYAL(厚声)")
      )
      (libsource (lib "easyedapro") (part "0402WGF499KTCE"))
    )
    (comp (ref "R29")
      (value "4.99Ω")
      (footprint "easyedapro:R0402")
      (description "电阻类型:厚膜电阻;阻值:4.99Ω;精度:±1%;功率:62.5mW;最大工作电压:50V;温度系数:±400ppm/°C;")
      (fields
        (field (name "Manufacturer Part") "0402WGF499KTCE")
        (field (name "Manufacturer") "UNI-ROYAL(厚声)")
      )
      (libsource (lib "easyedapro") (part "0402WGF499KTCE"))
    )
    (comp (ref "R30")
      (value "20kΩ")
      (footprint "easyedapro:R0402")
      (description "电阻类型:厚膜电阻;阻值:20kΩ;精度:±1%;功率:62.5mW;最大工作电压:50V;温度系数:±100ppm/°C;")
      (fields
        (field (name "Manufacturer Part") "0402WGF2002TCE")
        (field (name "Manufacturer") "UNI-ROYAL(厚声)")
      )
      (libsource (lib "easyedapro") (part "0402WGF2002TCE"))
    )
    (comp (ref "R31")
      (value "1kΩ")
      (footprint "easyedapro:R0402")
      (description "电阻类型:厚膜电阻;阻值:1kΩ;精度:±1%;功率:62.5mW;最大工作电压:50V;温度系数:±100ppm/°C;")
      (fields
        (field (name "Manufacturer Part") "0402WGF1001TCE")
        (field (name "Manufacturer") "UNI-ROYAL(厚声)")
      )
      (libsource (lib "easyedapro") (part "0402WGF1001TCE"))
    )
    (comp (ref "R32")
      (value "1kΩ")
      (footprint "easyedapro:R0402")
      (description "电阻类型:厚膜电阻;阻值:1kΩ;精度:±1%;功率:62.5mW;最大工作电压:50V;温度系数:±100ppm/°C;")
      (fields
        (field (name "Manufacturer Part") "0402WGF1001TCE")
        (field (name "Manufacturer") "UNI-ROYAL(厚声)")
      )
      (libsource (lib "easyedapro") (part "0402WGF1001TCE"))
    )
    (comp (ref "R33")
      (value "22Ω")
      (footprint "easyedapro:R0402")
      (description "电阻类型:厚膜电阻;阻值:22Ω;精度:±1%;功率:62.5mW;最大工作电压:50V;温度系数:±100ppm/°C;")
      (fields
        (field (name "Manufacturer Part") "0402WGF220JTCE")
        (field (name "Manufacturer") "UNI-ROYAL(厚声)")
      )
      (libsource (lib "easyedapro") (part "0402WGF220JTCE"))
    )
    (comp (ref "R34")
      (value "82Ω")
      (footprint "easyedapro:R0402")
      (description "电阻类型:厚膜电阻;阻值:82Ω;精度:±1%;功率:62.5mW;最大工作电压:50V;温度系数:±200ppm/°C;")
      (fields
        (field (name "Manufacturer Part") "0402WGF820JTCE")
        (field (name "Manufacturer") "UNI-ROYAL(厚声)")
      )
      (libsource (lib "easyedapro") (part "0402WGF820JTCE"))
    )
    (comp (ref "R35")
      (value "180Ω")
      (footprint "easyedapro:R0402")
      (description "电阻类型:厚膜电阻;阻值:180Ω;精度:±1%;功率:62.5mW;最大工作电压:50V;温度系数:±100ppm/°C;")
      (fields
        (field (name "Manufacturer Part") "0402WGF1800TCE")
        (field (name "Manufacturer") "UNI-ROYAL(厚声)")
      )
      (libsource (lib "easyedapro") (part "0402WGF1800TCE"))
    )
    (comp (ref "R36")
      (value "180Ω")
      (footprint "easyedapro:R0402")
      (description "电阻类型:厚膜电阻;阻值:180Ω;精度:±1%;功率:62.5mW;最大工作电压:50V;温度系数:±100ppm/°C;")
      (fields
        (field (name "Manufacturer Part") "0402WGF1800TCE")
        (field (name "Manufacturer") "UNI-ROYAL(厚声)")
      )
      (libsource (lib "easyedapro") (part "0402WGF1800TCE"))
    )
    (comp (ref "R37")
      (value "220Ω")
      (footprint "easyedapro:R0402")
      (description "电阻类型:厚膜电阻;阻值:220Ω;精度:±1%;功率:62.5mW;最大工作电压:50V;温度系数:±100ppm/°C;")
      (fields
        (field (name "Manufacturer Part") "0402WGF2200TCE")
        (field (name "Manufacturer") "UNI-ROYAL(厚声)")
      )
      (libsource (lib "easyedapro") (part "0402WGF2200TCE"))
    )
    (comp (ref "R38")
      (value "220Ω")
      (footprint "easyedapro:R0402")
      (description "电阻类型:厚膜电阻;阻值:220Ω;精度:±1%;功率:62.5mW;最大工作电压:50V;温度系数:±100ppm/°C;")
      (fields
        (field (name "Manufacturer Part") "0402WGF2200TCE")
        (field (name "Manufacturer") "UNI-ROYAL(厚声)")
      )
      (libsource (lib "easyedapro") (part "0402WGF2200TCE"))
    )
    (comp (ref "R39")
      (value "220Ω")
      (footprint "easyedapro:R0402")
      (description "电阻类型:厚膜电阻;阻值:220Ω;精度:±1%;功率:62.5mW;最大工作电压:50V;温度系数:±100ppm/°C;")
      (fields
        (field (name "Manufacturer Part") "0402WGF2200TCE")
        (field (name "Manufacturer") "UNI-ROYAL(厚声)")
      )
      (libsource (lib "easyedapro") (part "0402WGF2200TCE"))
    )
    (comp (ref "R40")
      (value "220Ω")
      (footprint "easyedapro:R0402")
      (description "电阻类型:厚膜电阻;阻值:220Ω;精度:±1%;功率:62.5mW;最大工作电压:50V;温度系数:±100ppm/°C;")
      (fields
        (field (name "Manufacturer Part") "0402WGF2200TCE")
        (field (name "Manufacturer") "UNI-ROYAL(厚声)")
      )
      (libsource (lib "easyedapro") (part "0402WGF2200TCE"))
    )
    (comp (ref "RF3")
      (value "BWSMA-KE-Z001")
      (footprint "easyedapro:SMA-TH_BWSMA-KE-Z001")
      (fields (field (name "Manufacturer") "BAT WIRELESS(蝙蝠无线)"))
      (libsource (lib "easyedapro") (part "BWSMA-KE-Z001"))
    )
    (comp (ref "RF4")
      (value "BWSMA-KE-Z001")
      (footprint "easyedapro:SMA-TH_BWSMA-KE-Z001")
      (fields (field (name "Manufacturer") "BAT WIRELESS(蝙蝠无线)"))
      (libsource (lib "easyedapro") (part "BWSMA-KE-Z001"))
    )
    (comp (ref "U8")
      (value "0-50uf")
      (footprint "easyedapro:可调电容")
      (libsource (lib "easyedapro") (part "0-50uf可调电容"))
    )
    (comp (ref "U9")
      (value "TLP172GM(TPL,E(O")
      (footprint "easyedapro:SMD-4_L4.6-W3.7-P2.54-LS7.0-BR")
      (description "继电器触点形式:1 Form A(SPST-NO);适用负载类型:AC,DC;正向压降:1.27V;负载电压:350V;连续负载电流:110mA;导通电阻:22Ω;")
      (fields (field (name "Manufacturer") "TOSHIBA(东芝)"))
      (libsource (lib "easyedapro") (part "TLP172GM(TPL,E(O"))
    )
    (comp (ref "U10")
      (value "GS8091-TR")
      (footprint "easyedapro:SOT-23-5_L3.0-W1.7-P0.95-LS2.8-BR")
      (description "放大器数:单路;增益带宽积(GBP):180MHz;输入偏置电流(Ib):1pA;输入失调电压(Vos):2mV;压摆率(SR):206V/us;带宽(-3db):350MHz;")
      (fields (field (name "Manufacturer") "Gainsil(聚洵)"))
      (libsource (lib "easyedapro") (part "GS8091-TR"))
    )
    (comp (ref "U11")
      (value "74HC4051PW,118")
      (footprint "easyedapro:TSSOP-16_L5.0-W4.4-P0.65-LS6.4-BL")
      (description "通道数:1;导通电阻(Ron@VCC):120Ω;")
      (fields (field (name "Manufacturer") "Nexperia(安世)"))
      (libsource (lib "easyedapro") (part "74HC4051PW,118"))
    )
    (comp (ref "U12")
      (value "GS8091-TR")
      (footprint "easyedapro:SOT-23-5_L3.0-W1.7-P0.95-LS2.8-BR")
      (description "放大器数:单路;增益带宽积(GBP):180MHz;输入偏置电流(Ib):1pA;输入失调电压(Vos):2mV;压摆率(SR):206V/us;带宽(-3db):350MHz;")
      (fields (field (name "Manufacturer") "Gainsil(聚洵)"))
      (libsource (lib "easyedapro") (part "GS8091-TR"))
    )
    (comp (ref "U13")
      (value "GS8091-TR")
      (footprint "easyedapro:SOT-23-5_L3.0-W1.7-P0.95-LS2.8-BR")
      (description "放大器数:单路;增益带宽积(GBP):180MHz;输入偏置电流(Ib):1pA;输入失调电压(Vos):2mV;压摆率(SR):206V/us;带宽(-3db):350MHz;")
      (fields (field (name "Manufacturer") "Gainsil(聚洵)"))
      (libsource (lib "easyedapro") (part "GS8091-TR"))
    )
    (comp (ref "U14")
      (value "GS8091-TR")
      (footprint "easyedapro:SOT-23-5_L3.0-W1.7-P0.95-LS2.8-BR")
      (description "放大器数:单路;增益带宽积(GBP):180MHz;输入偏置电流(Ib):1pA;输入失调电压(Vos):2mV;压摆率(SR):206V/us;带宽(-3db):350MHz;")
      (fields (field (name "Manufacturer") "Gainsil(聚洵)"))
      (libsource (lib "easyedapro") (part "GS8091-TR"))
    )
    (comp (ref "C27")
      (value "22uF")
      (footprint "easyedapro:C0603")
      (description "容值:22uF;精度:±20%;额定电压:6.3V;材质(温度系数):X5R;")
      (fields
        (field (name "Manufacturer Part") "CL10A226MQ8NRNC")
        (field (name "Manufacturer") "SAMSUNG(三星)")
      )
      (libsource (lib "easyedapro") (part "CL10A226MQ8NRNC"))
    )
    (comp (ref "C28")
      (value "22uF")
      (footprint "easyedapro:C0603")
      (description "容值:22uF;精度:±20%;额定电压:6.3V;材质(温度系数):X5R;")
      (fields
        (field (name "Manufacturer Part") "CL10A226MQ8NRNC")
        (field (name "Manufacturer") "SAMSUNG(三星)")
      )
      (libsource (lib "easyedapro") (part "CL10A226MQ8NRNC"))
    )
    (comp (ref "C29")
      (value "22uF")
      (footprint "easyedapro:C0603")
      (description "容值:22uF;精度:±20%;额定电压:6.3V;材质(温度系数):X5R;")
      (fields
        (field (name "Manufacturer Part") "CL10A226MQ8NRNC")
        (field (name "Manufacturer") "SAMSUNG(三星)")
      )
      (libsource (lib "easyedapro") (part "CL10A226MQ8NRNC"))
    )
    (comp (ref "C30")
      (value "100nF")
      (footprint "easyedapro:C0402")
      (description "容值:100nF;精度:±10%;额定电压:16V;材质(温度系数):X7R;")
      (fields
        (field (name "Manufacturer Part") "CL05B104KO5NNNC")
        (field (name "Manufacturer") "SAMSUNG(三星)")
      )
      (libsource (lib "easyedapro") (part "CL05B104KO5NNNC"))
    )
    (comp (ref "C31")
      (value "3.3uF")
      (footprint "easyedapro:C0603")
      (description "容值:3.3uF;精度:±10%;额定电压:10V;材质(温度系数):X5R;")
      (fields
        (field (name "Manufacturer Part") "CL10A335KP8NNNC")
        (field (name "Manufacturer") "SAMSUNG(三星)")
      )
      (libsource (lib "easyedapro") (part "CL10A335KP8NNNC"))
    )
    (comp (ref "J5")
      (value "~")
      (footprint "easyedapro:CH2.54-3插座")
      (libsource (lib "easyedapro") (part "HDR-3P"))
    )
    (comp (ref "U15")
      (value "SGM3204YN6G/TR")
      (footprint "easyedapro:SOT-23-6_L2.9-W1.6-P0.95-LS2.8-BR")
      (description "电荷泵芯片，开关电容式电压变换器，最大输出200mA,可用于运放放大、滤波等电路")
      (fields (field (name "Manufacturer") "SGMICRO(圣邦微)"))
      (libsource (lib "easyedapro") (part "SGM3204YN6G/TR"))
    )
  )
  (nets
    (net (code "1") (name "+3V3") (class "Default")
      (node (ref "C11") (pin "1") (pinfunction "1_1") (pintype "input"))
      (node (ref "C12") (pin "1") (pinfunction "1_1") (pintype "input"))
      (node (ref "C13") (pin "1") (pinfunction "1_1") (pintype "input"))
      (node (ref "C18") (pin "1") (pinfunction "1_1") (pintype "input"))
      (node (ref "C19") (pin "2") (pinfunction "2_2") (pintype "input"))
      (node (ref "C24") (pin "1") (pinfunction "1_1") (pintype "input"))
      (node (ref "C25") (pin "1") (pinfunction "1_1") (pintype "input"))
      (node (ref "C26") (pin "1") (pinfunction "1_1") (pintype "input"))
      (node (ref "C29") (pin "2") (pinfunction "2_2") (pintype "unspecified"))
      (node (ref "C5") (pin "1") (pinfunction "1_1") (pintype "input"))
      (node (ref "C6") (pin "2") (pinfunction "2_2") (pintype "input"))
      (node (ref "D2") (pin "1") (pinfunction "C_1") (pintype "unspecified"))
      (node (ref "D4") (pin "1") (pinfunction "C_1") (pintype "unspecified"))
      (node (ref "J5") (pin "3") (pinfunction "3_3") (pintype "input"))
      (node (ref "K1") (pin "1") (pinfunction "1_1") (pintype "unspecified"))
      (node (ref "K2") (pin "1") (pinfunction "1_1") (pintype "unspecified"))
      (node (ref "U10") (pin "5") (pinfunction "VDD_5") (pintype "unspecified"))
      (node (ref "U11") (pin "16") (pinfunction "VCC_16") (pintype "unspecified"))
      (node (ref "U12") (pin "5") (pinfunction "VDD_5") (pintype "unspecified"))
      (node (ref "U13") (pin "5") (pinfunction "VDD_5") (pintype "unspecified"))
      (node (ref "U14") (pin "5") (pinfunction "VDD_5") (pintype "unspecified"))
      (node (ref "U15") (pin "2") (pinfunction "IN_2") (pintype "unspecified"))
      (node (ref "U15") (pin "5") (pinfunction "EN_5") (pintype "unspecified"))
      (node (ref "U3") (pin "5") (pinfunction "VDD_5") (pintype "unspecified"))
      (node (ref "U4") (pin "16") (pinfunction "VCC_16") (pintype "unspecified"))
      (node (ref "U5") (pin "5") (pinfunction "VDD_5") (pintype "unspecified"))
      (node (ref "U6") (pin "5") (pinfunction "VDD_5") (pintype "unspecified"))
      (node (ref "U7") (pin "5") (pinfunction "VDD_5") (pintype "unspecified"))
    )
    (net (code "2") (name "-3V3") (class "Default")
      (node (ref "C10") (pin "1") (pinfunction "1_1") (pintype "input"))
      (node (ref "C15") (pin "1") (pinfunction "1_1") (pintype "input"))
      (node (ref "C2") (pin "1") (pinfunction "1_1") (pintype "input"))
      (node (ref "C20") (pin "1") (pinfunction "1_1") (pintype "input"))
      (node (ref "C21") (pin "1") (pinfunction "1_1") (pintype "input"))
      (node (ref "C22") (pin "2") (pinfunction "2_2") (pintype "input"))
      (node (ref "C23") (pin "1") (pinfunction "1_1") (pintype "input"))
      (node (ref "C27") (pin "2") (pinfunction "2_2") (pintype "unspecified"))
      (node (ref "C28") (pin "2") (pinfunction "2_2") (pintype "unspecified"))
      (node (ref "C30") (pin "2") (pinfunction "2_2") (pintype "unspecified"))
      (node (ref "C7") (pin "1") (pinfunction "1_1") (pintype "input"))
      (node (ref "C8") (pin "1") (pinfunction "1_1") (pintype "input"))
      (node (ref "C9") (pin "2") (pinfunction "2_2") (pintype "input"))
      (node (ref "D1") (pin "2") (pinfunction "A_2") (pintype "unspecified"))
      (node (ref "D3") (pin "2") (pinfunction "A_2") (pintype "unspecified"))
      (node (ref "U10") (pin "2") (pinfunction "VSS_2") (pintype "unspecified"))
      (node (ref "U11") (pin "7") (pinfunction "VEE_7") (pintype "unspecified"))
      (node (ref "U12") (pin "2") (pinfunction "VSS_2") (pintype "unspecified"))
      (node (ref "U13") (pin "2") (pinfunction "VSS_2") (pintype "unspecified"))
      (node (ref "U14") (pin "2") (pinfunction "VSS_2") (pintype "unspecified"))
      (node (ref "U15") (pin "1") (pinfunction "OUT_1") (pintype "unspecified"))
      (node (ref "U3") (pin "2") (pinfunction "VSS_2") (pintype "unspecified"))
      (node (ref "U4") (pin "7") (pinfunction "VEE_7") (pintype "unspecified"))
      (node (ref "U5") (pin "2") (pinfunction "VSS_2") (pintype "unspecified"))
      (node (ref "U6") (pin "2") (pinfunction "VSS_2") (pintype "unspecified"))
      (node (ref "U7") (pin "2") (pinfunction "VSS_2") (pintype "unspecified"))
    )
    (net (code "3") (name "CH1-0") (class "Default")
      (node (ref "R4") (pin "1") (pinfunction "1_1") (pintype "input"))
      (node (ref "U3") (pin "1") (pinfunction "OUT_1") (pintype "unspecified"))
      (node (ref "U3") (pin "4") (pinfunction "IN-_4") (pintype "unspecified"))
      (node (ref "U4") (pin "1") (pinfunction "Y4_1") (pintype "unspecified"))
    )
    (net (code "4") (name "CH1-1") (class "Default")
      (node (ref "R4") (pin "2") (pinfunction "2_2") (pintype "input"))
      (node (ref "R5") (pin "1") (pinfunction "1_1") (pintype "input"))
      (node (ref "U4") (pin "2") (pinfunction "Y6_2") (pintype "unspecified"))
    )
    (net (code "5") (name "CH1-2") (class "Default")
      (node (ref "R5") (pin "2") (pinfunction "2_2") (pintype "input"))
      (node (ref "R6") (pin "1") (pinfunction "1_1") (pintype "input"))
      (node (ref "U4") (pin "15") (pinfunction "Y2_15") (pintype "unspecified"))
    )
    (net (code "6") (name "CH1-3") (class "Default")
      (node (ref "R6") (pin "2") (pinfunction "2_2") (pintype "input"))
      (node (ref "R7") (pin "1") (pinfunction "1_1") (pintype "input"))
      (node (ref "U4") (pin "14") (pinfunction "Y1_14") (pintype "unspecified"))
    )
    (net (code "7") (name "CH1-4") (class "Default")
      (node (ref "R7") (pin "2") (pinfunction "2_2") (pintype "input"))
      (node (ref "R8") (pin "1") (pinfunction "1_1") (pintype "input"))
      (node (ref "U4") (pin "12") (pinfunction "Y3_12") (pintype "unspecified"))
    )
    (net (code "8") (name "CH1-5") (class "Default")
      (node (ref "R8") (pin "2") (pinfunction "2_2") (pintype "input"))
      (node (ref "R9") (pin "1") (pinfunction "1_1") (pintype "input"))
      (node (ref "U4") (pin "13") (pinfunction "Y0_13") (pintype "unspecified"))
    )
    (net (code "9") (name "CH1-OUT") (class "Default")
      (node (ref "R13") (pin "2") (pinfunction "2_2") (pintype "input"))
      (node (ref "RF2") (pin "5") (pinfunction "5_5") (pintype "unspecified"))
    )
    (net (code "10") (name "CH2-0") (class "Default")
      (node (ref "R24") (pin "1") (pinfunction "1_1") (pintype "input"))
      (node (ref "U10") (pin "1") (pinfunction "OUT_1") (pintype "unspecified"))
      (node (ref "U10") (pin "4") (pinfunction "IN-_4") (pintype "unspecified"))
      (node (ref "U11") (pin "5") (pinfunction "Y5_5") (pintype "unspecified"))
    )
    (net (code "11") (name "CH2-1") (class "Default")
      (node (ref "R24") (pin "2") (pinfunction "2_2") (pintype "input"))
      (node (ref "R25") (pin "1") (pinfunction "1_1") (pintype "input"))
      (node (ref "U11") (pin "4") (pinfunction "Y7_4") (pintype "unspecified"))
    )
    (net (code "12") (name "CH2-2") (class "Default")
      (node (ref "R25") (pin "2") (pinfunction "2_2") (pintype "input"))
      (node (ref "R26") (pin "1") (pinfunction "1_1") (pintype "input"))
      (node (ref "U11") (pin "12") (pinfunction "Y3_12") (pintype "unspecified"))
    )
    (net (code "13") (name "CH2-3") (class "Default")
      (node (ref "R26") (pin "2") (pinfunction "2_2") (pintype "input"))
      (node (ref "R27") (pin "1") (pinfunction "1_1") (pintype "input"))
      (node (ref "U11") (pin "13") (pinfunction "Y0_13") (pintype "unspecified"))
    )
    (net (code "14") (name "CH2-4") (class "Default")
      (node (ref "R27") (pin "2") (pinfunction "2_2") (pintype "input"))
      (node (ref "R28") (pin "1") (pinfunction "1_1") (pintype "input"))
      (node (ref "U11") (pin "14") (pinfunction "Y1_14") (pintype "unspecified"))
    )
    (net (code "15") (name "CH2-5") (class "Default")
      (node (ref "R28") (pin "2") (pinfunction "2_2") (pintype "input"))
      (node (ref "R29") (pin "1") (pinfunction "1_1") (pintype "input"))
      (node (ref "U11") (pin "15") (pinfunction "Y2_15") (pintype "unspecified"))
    )
    (net (code "16") (name "CH2-OUT") (class "Default")
      (node (ref "R33") (pin "2") (pinfunction "2_2") (pintype "input"))
      (node (ref "RF4") (pin "5") (pinfunction "5_5") (pintype "unspecified"))
    )
    (net (code "17") (name "DAC0") (class "Default")
      (node (ref "J1") (pin "2") (pinfunction "2_2") (pintype "input"))
      (node (ref "R19") (pin "1") (pinfunction "1_1") (pintype "input"))
    )
    (net (code "18") (name "DAC1") (class "Default")
      (node (ref "J3") (pin "2") (pinfunction "2_2") (pintype "input"))
      (node (ref "R39") (pin "1") (pinfunction "1_1") (pintype "input"))
    )
    (net (code "19") (name "DIO-RA0") (class "Default")
      (node (ref "J1") (pin "1") (pinfunction "1_1") (pintype "input"))
      (node (ref "U2") (pin "1") (pinfunction "1_1") (pintype "unspecified"))
    )
    (net (code "20") (name "DIO-RA1") (class "Default")
      (node (ref "J3") (pin "1") (pinfunction "1_1") (pintype "input"))
      (node (ref "U9") (pin "1") (pinfunction "1_1") (pintype "unspecified"))
    )
    (net (code "21") (name "GND") (class "Default")
      (node (ref "C10") (pin "2") (pinfunction "2_2") (pintype "input"))
      (node (ref "C11") (pin "2") (pinfunction "2_2") (pintype "input"))
      (node (ref "C12") (pin "2") (pinfunction "2_2") (pintype "input"))
      (node (ref "C13") (pin "2") (pinfunction "2_2") (pintype "input"))
      (node (ref "C15") (pin "2") (pinfunction "2_2") (pintype "input"))
      (node (ref "C17") (pin "1") (pinfunction "1_1") (pintype "unspecified"))
      (node (ref "C18") (pin "2") (pinfunction "2_2") (pintype "input"))
      (node (ref "C19") (pin "1") (pinfunction "1_1") (pintype "input"))
      (node (ref "C2") (pin "2") (pinfunction "2_2") (pintype "input"))
      (node (ref "C20") (pin "2") (pinfunction "2_2") (pintype "input"))
      (node (ref "C21") (pin "2") (pinfunction "2_2") (pintype "input"))
      (node (ref "C22") (pin "1") (pinfunction "1_1") (pintype "input"))
      (node (ref "C23") (pin "2") (pinfunction "2_2") (pintype "input"))
      (node (ref "C24") (pin "2") (pinfunction "2_2") (pintype "input"))
      (node (ref "C25") (pin "2") (pinfunction "2_2") (pintype "input"))
      (node (ref "C26") (pin "2") (pinfunction "2_2") (pintype "input"))
      (node (ref "C27") (pin "1") (pinfunction "1_1") (pintype "unspecified"))
      (node (ref "C28") (pin "1") (pinfunction "1_1") (pintype "unspecified"))
      (node (ref "C29") (pin "1") (pinfunction "1_1") (pintype "unspecified"))
      (node (ref "C30") (pin "1") (pinfunction "1_1") (pintype "unspecified"))
      (node (ref "C4") (pin "1") (pinfunction "1_1") (pintype "unspecified"))
      (node (ref "C5") (pin "2") (pinfunction "2_2") (pintype "input"))
      (node (ref "C6") (pin "1") (pinfunction "1_1") (pintype "input"))
      (node (ref "C7") (pin "2") (pinfunction "2_2") (pintype "input"))
      (node (ref "C8") (pin "2") (pinfunction "2_2") (pintype "input"))
      (node (ref "C9") (pin "1") (pinfunction "1_1") (pintype "input"))
      (node (ref "J5") (pin "1") (pinfunction "1_1") (pintype "input"))
      (node (ref "J5") (pin "2") (pinfunction "2_2") (pintype "input"))
      (node (ref "R10") (pin "1") (pinfunction "1_1") (pintype "input"))
      (node (ref "R11") (pin "1") (pinfunction "1_1") (pintype "input"))
      (node (ref "R12") (pin "1") (pinfunction "1_1") (pintype "input"))
      (node (ref "R14") (pin "1") (pinfunction "1_1") (pintype "input"))
      (node (ref "R16") (pin "1") (pinfunction "1_1") (pintype "input"))
      (node (ref "R29") (pin "2") (pinfunction "2_2") (pintype "input"))
      (node (ref "R30") (pin "1") (pinfunction "1_1") (pintype "input"))
      (node (ref "R31") (pin "1") (pinfunction "1_1") (pintype "input"))
      (node (ref "R32") (pin "1") (pinfunction "1_1") (pintype "input"))
      (node (ref "R34") (pin "1") (pinfunction "1_1") (pintype "input"))
      (node (ref "R36") (pin "1") (pinfunction "1_1") (pintype "input"))
      (node (ref "R9") (pin "2") (pinfunction "2_2") (pintype "input"))
      (node (ref "RF1") (pin "1") (pinfunction "1_1") (pintype "unspecified"))
      (node (ref "RF1") (pin "2") (pinfunction "2_2") (pintype "unspecified"))
      (node (ref "RF1") (pin "3") (pinfunction "3_3") (pintype "unspecified"))
      (node (ref "RF1") (pin "4") (pinfunction "4_4") (pintype "unspecified"))
      (node (ref "RF2") (pin "1") (pinfunction "1_1") (pintype "unspecified"))
      (node (ref "RF2") (pin "2") (pinfunction "2_2") (pintype "unspecified"))
      (node (ref "RF2") (pin "3") (pinfunction "3_3") (pintype "unspecified"))
      (node (ref "RF2") (pin "4") (pinfunction "4_4") (pintype "unspecified"))
      (node (ref "RF3") (pin "1") (pinfunction "1_1") (pintype "unspecified"))
      (node (ref "RF3") (pin "2") (pinfunction "2_2") (pintype "unspecified"))
      (node (ref "RF3") (pin "3") (pinfunction "3_3") (pintype "unspecified"))
      (node (ref "RF3") (pin "4") (pinfunction "4_4") (pintype "unspecified"))
      (node (ref "RF4") (pin "1") (pinfunction "1_1") (pintype "unspecified"))
      (node (ref "RF4") (pin "2") (pinfunction "2_2") (pintype "unspecified"))
      (node (ref "RF4") (pin "3") (pinfunction "3_3") (pintype "unspecified"))
      (node (ref "RF4") (pin "4") (pinfunction "4_4") (pintype "unspecified"))
      (node (ref "U11") (pin "6") (pinfunction "E#_6") (pintype "unspecified"))
      (node (ref "U11") (pin "8") (pinfunction "GND_8") (pintype "unspecified"))
      (node (ref "U14") (pin "3") (pinfunction "IN+_3") (pintype "unspecified"))
      (node (ref "U15") (pin "4") (pinfunction "GND_4") (pintype "unspecified"))
      (node (ref "U4") (pin "6") (pinfunction "E#_6") (pintype "unspecified"))
      (node (ref "U4") (pin "8") (pinfunction "GND_8") (pintype "unspecified"))
      (node (ref "U7") (pin "3") (pinfunction "IN+_3") (pintype "unspecified"))
    )
    (net (code "22") (name "HC-A0") (class "Default")
      (node (ref "J2") (pin "3") (pinfunction "3_3") (pintype "input"))
      (node (ref "U4") (pin "11") (pinfunction "S0_11") (pintype "unspecified"))
    )
    (net (code "23") (name "HC-A1") (class "Default")
      (node (ref "J4") (pin "3") (pinfunction "3_3") (pintype "input"))
      (node (ref "U11") (pin "11") (pinfunction "S0_11") (pintype "unspecified"))
    )
    (net (code "24") (name "HC-B0") (class "Default")
      (node (ref "J2") (pin "2") (pinfunction "2_2") (pintype "input"))
      (node (ref "U4") (pin "10") (pinfunction "S1_10") (pintype "unspecified"))
    )
    (net (code "25") (name "HC-B1") (class "Default")
      (node (ref "J4") (pin "2") (pinfunction "2_2") (pintype "input"))
      (node (ref "U11") (pin "10") (pinfunction "S1_10") (pintype "unspecified"))
    )
    (net (code "26") (name "HC-C0") (class "Default")
      (node (ref "J2") (pin "1") (pinfunction "1_1") (pintype "input"))
      (node (ref "U4") (pin "9") (pinfunction "S2_9") (pintype "unspecified"))
    )
    (net (code "27") (name "HC-C1") (class "Default")
      (node (ref "J4") (pin "1") (pinfunction "1_1") (pintype "input"))
      (node (ref "U11") (pin "9") (pinfunction "S2_9") (pintype "unspecified"))
    )
    (net (code "28") (name "Net-(C1-Pad2)") (class "Default")
      (node (ref "C1") (pin "2") (pinfunction "2_2") (pintype "input"))
      (node (ref "C3") (pin "1") (pinfunction "1_1") (pintype "input"))
      (node (ref "R1") (pin "2") (pinfunction "2_2") (pintype "input"))
      (node (ref "R2") (pin "2") (pinfunction "2_2") (pintype "input"))
      (node (ref "U1") (pin "2") (pinfunction "2_2") (pintype "unspecified"))
      (node (ref "U2") (pin "3") (pinfunction "3_3") (pintype "unspecified"))
    )
    (net (code "29") (name "Net-(C3-Pad2)") (class "Default")
      (node (ref "C3") (pin "2") (pinfunction "2_2") (pintype "input"))
      (node (ref "K1") (pin "4") (pinfunction "4_4") (pintype "unspecified"))
      (node (ref "R1") (pin "1") (pinfunction "1_1") (pintype "input"))
    )
    (net (code "30") (name "Net-(C4-Pad2)") (class "Default")
      (node (ref "C4") (pin "2") (pinfunction "2_2") (pintype "unspecified"))
      (node (ref "K1") (pin "2") (pinfunction "2_2") (pintype "unspecified"))
      (node (ref "R10") (pin "2") (pinfunction "2_2") (pintype "input"))
      (node (ref "R3") (pin "1") (pinfunction "1_1") (pintype "input"))
      (node (ref "U1") (pin "1") (pinfunction "1_1") (pintype "unspecified"))
    )
    (net (code "31") (name "Net-(C14-Pad2)") (class "Default")
      (node (ref "C14") (pin "2") (pinfunction "2_2") (pintype "input"))
      (node (ref "C16") (pin "1") (pinfunction "1_1") (pintype "input"))
      (node (ref "R21") (pin "2") (pinfunction "2_2") (pintype "input"))
      (node (ref "R22") (pin "2") (pinfunction "2_2") (pintype "input"))
      (node (ref "U8") (pin "2") (pinfunction "2_2") (pintype "unspecified"))
      (node (ref "U9") (pin "3") (pinfunction "3_3") (pintype "unspecified"))
    )
    (net (code "32") (name "Net-(C16-Pad2)") (class "Default")
      (node (ref "C16") (pin "2") (pinfunction "2_2") (pintype "input"))
      (node (ref "K2") (pin "4") (pinfunction "4_4") (pintype "unspecified"))
      (node (ref "R21") (pin "1") (pinfunction "1_1") (pintype "input"))
    )
    (net (code "33") (name "Net-(C17-Pad2)") (class "Default")
      (node (ref "C17") (pin "2") (pinfunction "2_2") (pintype "unspecified"))
      (node (ref "K2") (pin "2") (pinfunction "2_2") (pintype "unspecified"))
      (node (ref "R23") (pin "1") (pinfunction "1_1") (pintype "input"))
      (node (ref "R30") (pin "2") (pinfunction "2_2") (pintype "input"))
      (node (ref "U8") (pin "1") (pinfunction "1_1") (pintype "unspecified"))
    )
    (net (code "34") (name "Net-(D1-C)") (class "Default")
      (node (ref "D1") (pin "1") (pinfunction "C_1") (pintype "unspecified"))
      (node (ref "D2") (pin "2") (pinfunction "A_2") (pintype "unspecified"))
      (node (ref "K1") (pin "3") (pinfunction "3_3") (pintype "unspecified"))
      (node (ref "U3") (pin "3") (pinfunction "IN+_3") (pintype "unspecified"))
    )
    (net (code "35") (name "Net-(D3-C)") (class "Default")
      (node (ref "D3") (pin "1") (pinfunction "C_1") (pintype "unspecified"))
      (node (ref "D4") (pin "2") (pinfunction "A_2") (pintype "unspecified"))
      (node (ref "K2") (pin "3") (pinfunction "3_3") (pintype "unspecified"))
      (node (ref "U10") (pin "3") (pinfunction "IN+_3") (pintype "unspecified"))
    )
    (net (code "36") (name "Net-(R2-Pad1)") (class "Default")
      (node (ref "R2") (pin "1") (pinfunction "1_1") (pintype "input"))
      (node (ref "R3") (pin "2") (pinfunction "2_2") (pintype "input"))
    )
    (net (code "37") (name "Net-(R11-Pad2)") (class "Default")
      (node (ref "R11") (pin "2") (pinfunction "2_2") (pintype "input"))
      (node (ref "R12") (pin "2") (pinfunction "2_2") (pintype "input"))
      (node (ref "U2") (pin "2") (pinfunction "2_2") (pintype "unspecified"))
    )
    (net (code "38") (name "Net-(R22-Pad1)") (class "Default")
      (node (ref "R22") (pin "1") (pinfunction "1_1") (pintype "input"))
      (node (ref "R23") (pin "2") (pinfunction "2_2") (pintype "input"))
    )
    (net (code "39") (name "Net-(R31-Pad2)") (class "Default")
      (node (ref "R31") (pin "2") (pinfunction "2_2") (pintype "input"))
      (node (ref "R32") (pin "2") (pinfunction "2_2") (pintype "input"))
      (node (ref "U9") (pin "2") (pinfunction "2_2") (pintype "unspecified"))
    )
    (net (code "40") (name "Net-(U5-IN-)") (class "Default")
      (node (ref "R14") (pin "2") (pinfunction "2_2") (pintype "input"))
      (node (ref "R15") (pin "1") (pinfunction "1_1") (pintype "input"))
      (node (ref "U5") (pin "4") (pinfunction "IN-_4") (pintype "unspecified"))
    )
    (net (code "41") (name "Net-(U5-OUT)") (class "Default")
      (node (ref "R15") (pin "2") (pinfunction "2_2") (pintype "input"))
      (node (ref "U5") (pin "1") (pinfunction "OUT_1") (pintype "unspecified"))
      (node (ref "U6") (pin "3") (pinfunction "IN+_3") (pintype "unspecified"))
    )
    (net (code "42") (name "Net-(U6-IN-)") (class "Default")
      (node (ref "R16") (pin "2") (pinfunction "2_2") (pintype "input"))
      (node (ref "R17") (pin "1") (pinfunction "1_1") (pintype "input"))
      (node (ref "R18") (pin "2") (pinfunction "2_2") (pintype "input"))
      (node (ref "U6") (pin "4") (pinfunction "IN-_4") (pintype "unspecified"))
    )
    (net (code "43") (name "Net-(U6-OUT)") (class "Default")
      (node (ref "R13") (pin "1") (pinfunction "1_1") (pintype "input"))
      (node (ref "R17") (pin "2") (pinfunction "2_2") (pintype "input"))
      (node (ref "U6") (pin "1") (pinfunction "OUT_1") (pintype "unspecified"))
    )
    (net (code "44") (name "Net-(U7-IN-)") (class "Default")
      (node (ref "R19") (pin "2") (pinfunction "2_2") (pintype "input"))
      (node (ref "R20") (pin "1") (pinfunction "1_1") (pintype "input"))
      (node (ref "U7") (pin "4") (pinfunction "IN-_4") (pintype "unspecified"))
    )
    (net (code "45") (name "Net-(U7-OUT)") (class "Default")
      (node (ref "R18") (pin "1") (pinfunction "1_1") (pintype "input"))
      (node (ref "R20") (pin "2") (pinfunction "2_2") (pintype "input"))
      (node (ref "U7") (pin "1") (pinfunction "OUT_1") (pintype "unspecified"))
    )
    (net (code "46") (name "Net-(U12-IN-)") (class "Default")
      (node (ref "R34") (pin "2") (pinfunction "2_2") (pintype "input"))
      (node (ref "R35") (pin "1") (pinfunction "1_1") (pintype "input"))
      (node (ref "U12") (pin "4") (pinfunction "IN-_4") (pintype "unspecified"))
    )
    (net (code "47") (name "Net-(U12-OUT)") (class "Default")
      (node (ref "R35") (pin "2") (pinfunction "2_2") (pintype "input"))
      (node (ref "U12") (pin "1") (pinfunction "OUT_1") (pintype "unspecified"))
      (node (ref "U13") (pin "3") (pinfunction "IN+_3") (pintype "unspecified"))
    )
    (net (code "48") (name "Net-(U13-IN-)") (class "Default")
      (node (ref "R36") (pin "2") (pinfunction "2_2") (pintype "input"))
      (node (ref "R37") (pin "1") (pinfunction "1_1") (pintype "input"))
      (node (ref "R38") (pin "2") (pinfunction "2_2") (pintype "input"))
      (node (ref "U13") (pin "4") (pinfunction "IN-_4") (pintype "unspecified"))
    )
    (net (code "49") (name "Net-(U13-OUT)") (class "Default")
      (node (ref "R33") (pin "1") (pinfunction "1_1") (pintype "input"))
      (node (ref "R37") (pin "2") (pinfunction "2_2") (pintype "input"))
      (node (ref "U13") (pin "1") (pinfunction "OUT_1") (pintype "unspecified"))
    )
    (net (code "50") (name "Net-(U14-IN-)") (class "Default")
      (node (ref "R39") (pin "2") (pinfunction "2_2") (pintype "input"))
      (node (ref "R40") (pin "1") (pinfunction "1_1") (pintype "input"))
      (node (ref "U14") (pin "4") (pinfunction "IN-_4") (pintype "unspecified"))
    )
    (net (code "51") (name "Net-(U14-OUT)") (class "Default")
      (node (ref "R38") (pin "1") (pinfunction "1_1") (pintype "input"))
      (node (ref "R40") (pin "2") (pinfunction "2_2") (pintype "input"))
      (node (ref "U14") (pin "1") (pinfunction "OUT_1") (pintype "unspecified"))
    )
    (net (code "52") (name "Net-(U15-CFLY+)") (class "Default")
      (node (ref "C31") (pin "2") (pinfunction "2_2") (pintype "input"))
      (node (ref "U15") (pin "6") (pinfunction "CFLY+_6") (pintype "unspecified"))
    )
    (net (code "53") (name "Net-(U15-CFLY-)") (class "Default")
      (node (ref "C31") (pin "1") (pinfunction "1_1") (pintype "input"))
      (node (ref "U15") (pin "3") (pinfunction "CFLY-_3") (pintype "unspecified"))
    )
    (net (code "54") (name "OUT_HC0") (class "Default")
      (node (ref "U4") (pin "3") (pinfunction "Z_3") (pintype "unspecified"))
      (node (ref "U5") (pin "3") (pinfunction "IN+_3") (pintype "unspecified"))
    )
    (net (code "55") (name "OUT_HC1") (class "Default")
      (node (ref "U11") (pin "3") (pinfunction "Z_3") (pintype "unspecified"))
      (node (ref "U12") (pin "3") (pinfunction "IN+_3") (pintype "unspecified"))
    )
    (net (code "56") (name "RLY0") (class "Default")
      (node (ref "J1") (pin "3") (pinfunction "3_3") (pintype "input"))
      (node (ref "K1") (pin "8") (pinfunction "8_8") (pintype "unspecified"))
    )
    (net (code "57") (name "RLY1") (class "Default")
      (node (ref "J3") (pin "3") (pinfunction "3_3") (pintype "input"))
      (node (ref "K2") (pin "8") (pinfunction "8_8") (pintype "unspecified"))
    )
    (net (code "58") (name "input1") (class "Default")
      (node (ref "C1") (pin "1") (pinfunction "1_1") (pintype "input"))
      (node (ref "RF1") (pin "5") (pinfunction "5_5") (pintype "unspecified"))
      (node (ref "U2") (pin "4") (pinfunction "4_4") (pintype "unspecified"))
    )
    (net (code "59") (name "input2") (class "Default")
      (node (ref "C14") (pin "1") (pinfunction "1_1") (pintype "input"))
      (node (ref "RF3") (pin "5") (pinfunction "5_5") (pintype "unspecified"))
      (node (ref "U9") (pin "4") (pinfunction "4_4") (pintype "unspecified"))
    )
    (net (code "60") (name "unconnected-(K1-Pad5)") (class "Default")
      (node (ref "K1") (pin "5") (pinfunction "5_5") (pintype "unspecified+no_connect"))
    )
    (net (code "61") (name "unconnected-(K1-Pad6)") (class "Default")
      (node (ref "K1") (pin "6") (pinfunction "6_6") (pintype "unspecified+no_connect"))
    )
    (net (code "62") (name "unconnected-(K1-Pad7)") (class "Default")
      (node (ref "K1") (pin "7") (pinfunction "7_7") (pintype "unspecified+no_connect"))
    )
    (net (code "63") (name "unconnected-(K2-Pad5)") (class "Default")
      (node (ref "K2") (pin "5") (pinfunction "5_5") (pintype "unspecified+no_connect"))
    )
    (net (code "64") (name "unconnected-(K2-Pad6)") (class "Default")
      (node (ref "K2") (pin "6") (pinfunction "6_6") (pintype "unspecified+no_connect"))
    )
    (net (code "65") (name "unconnected-(K2-Pad7)") (class "Default")
      (node (ref "K2") (pin "7") (pinfunction "7_7") (pintype "unspecified+no_connect"))
    )
    (net (code "66") (name "unconnected-(U4-Y5-Pad5)") (class "Default")
      (node (ref "U4") (pin "5") (pinfunction "Y5_5") (pintype "unspecified"))
    )
    (net (code "67") (name "unconnected-(U4-Y7-Pad4)") (class "Default")
      (node (ref "U4") (pin "4") (pinfunction "Y7_4") (pintype "unspecified"))
    )
    (net (code "68") (name "unconnected-(U11-Y4-Pad1)") (class "Default")
      (node (ref "U11") (pin "1") (pinfunction "Y4_1") (pintype "unspecified"))
    )
    (net (code "69") (name "unconnected-(U11-Y6-Pad2)") (class "Default")
      (node (ref "U11") (pin "2") (pinfunction "Y6_2") (pintype "unspecified"))
    )
  )
)
